# layer1.net
KiCad netlist of a schematic drawn in EAGLE
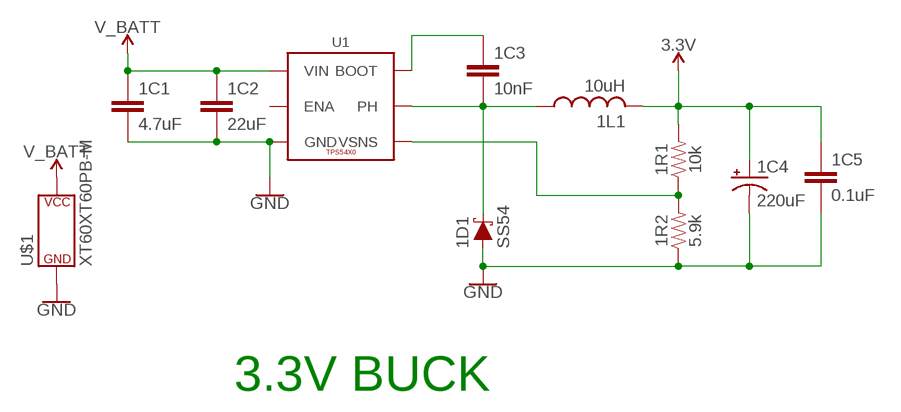
[diagram p0: schematic, sheet 1]
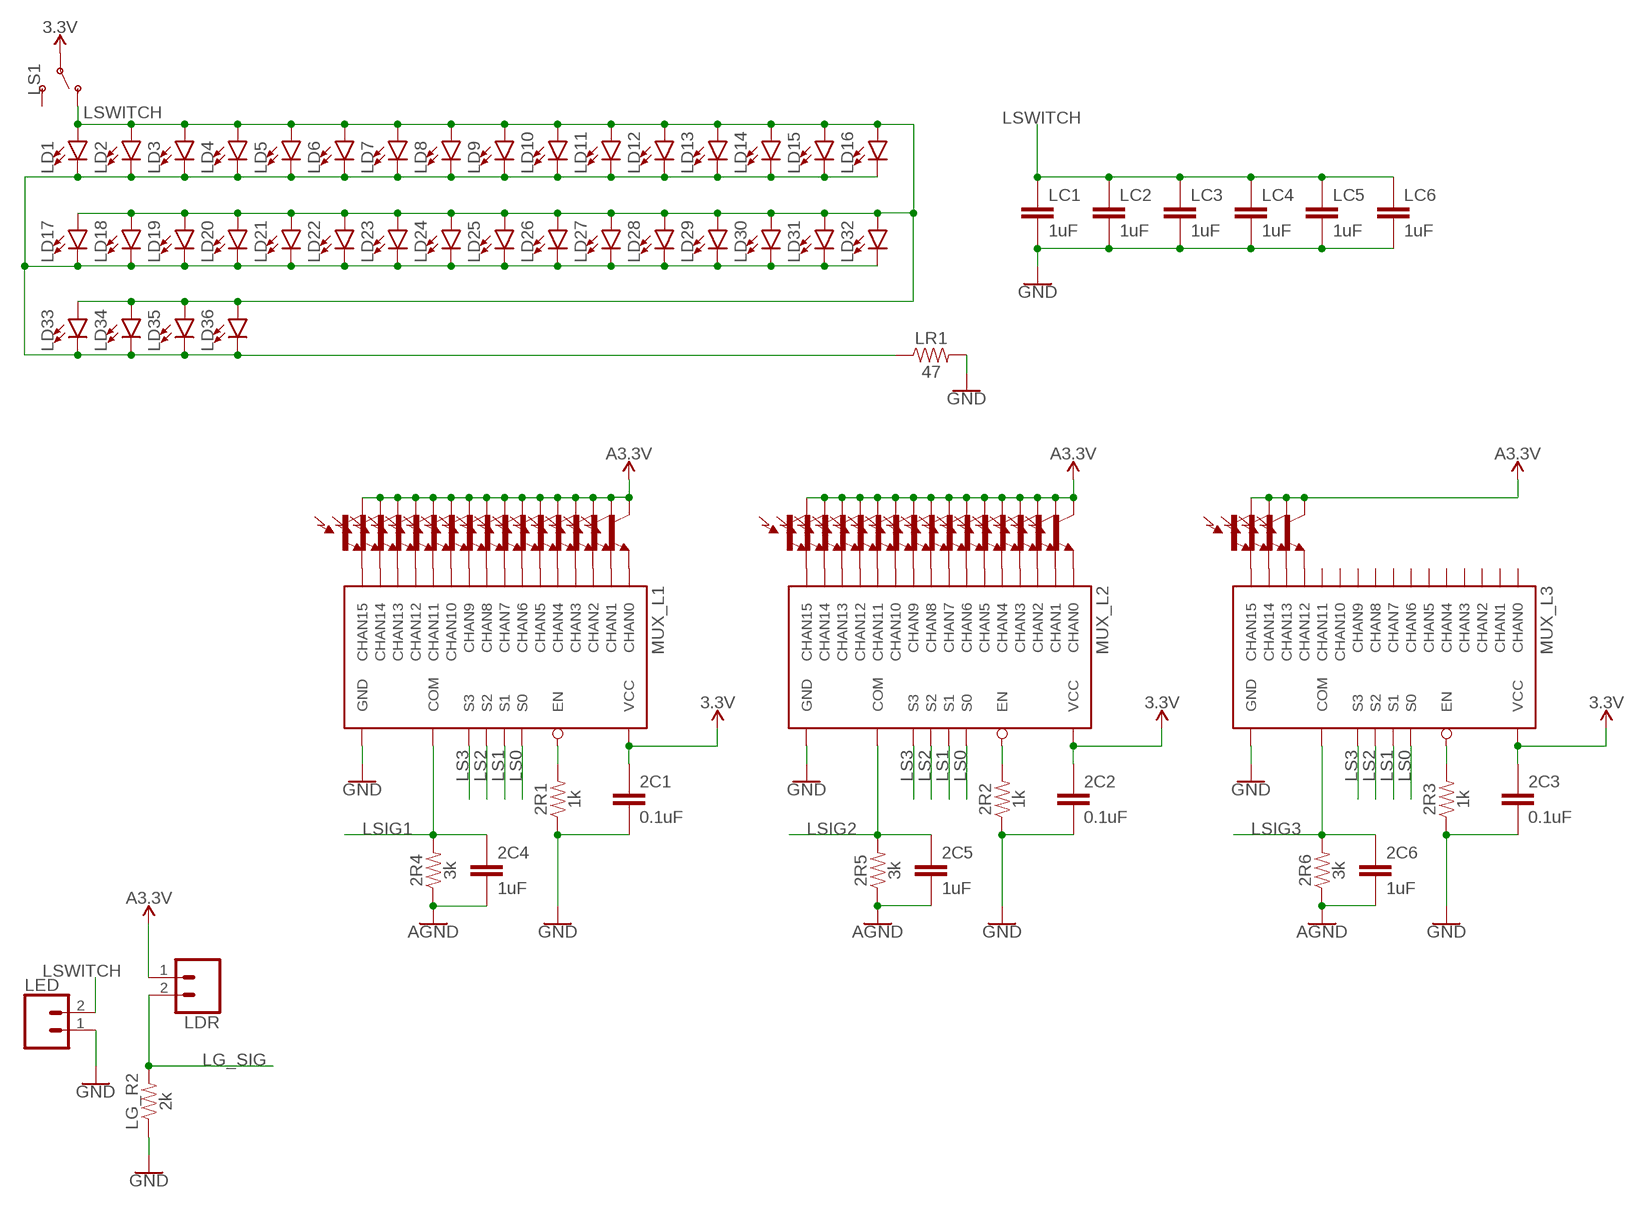
[diagram p1: schematic, sheet 2]
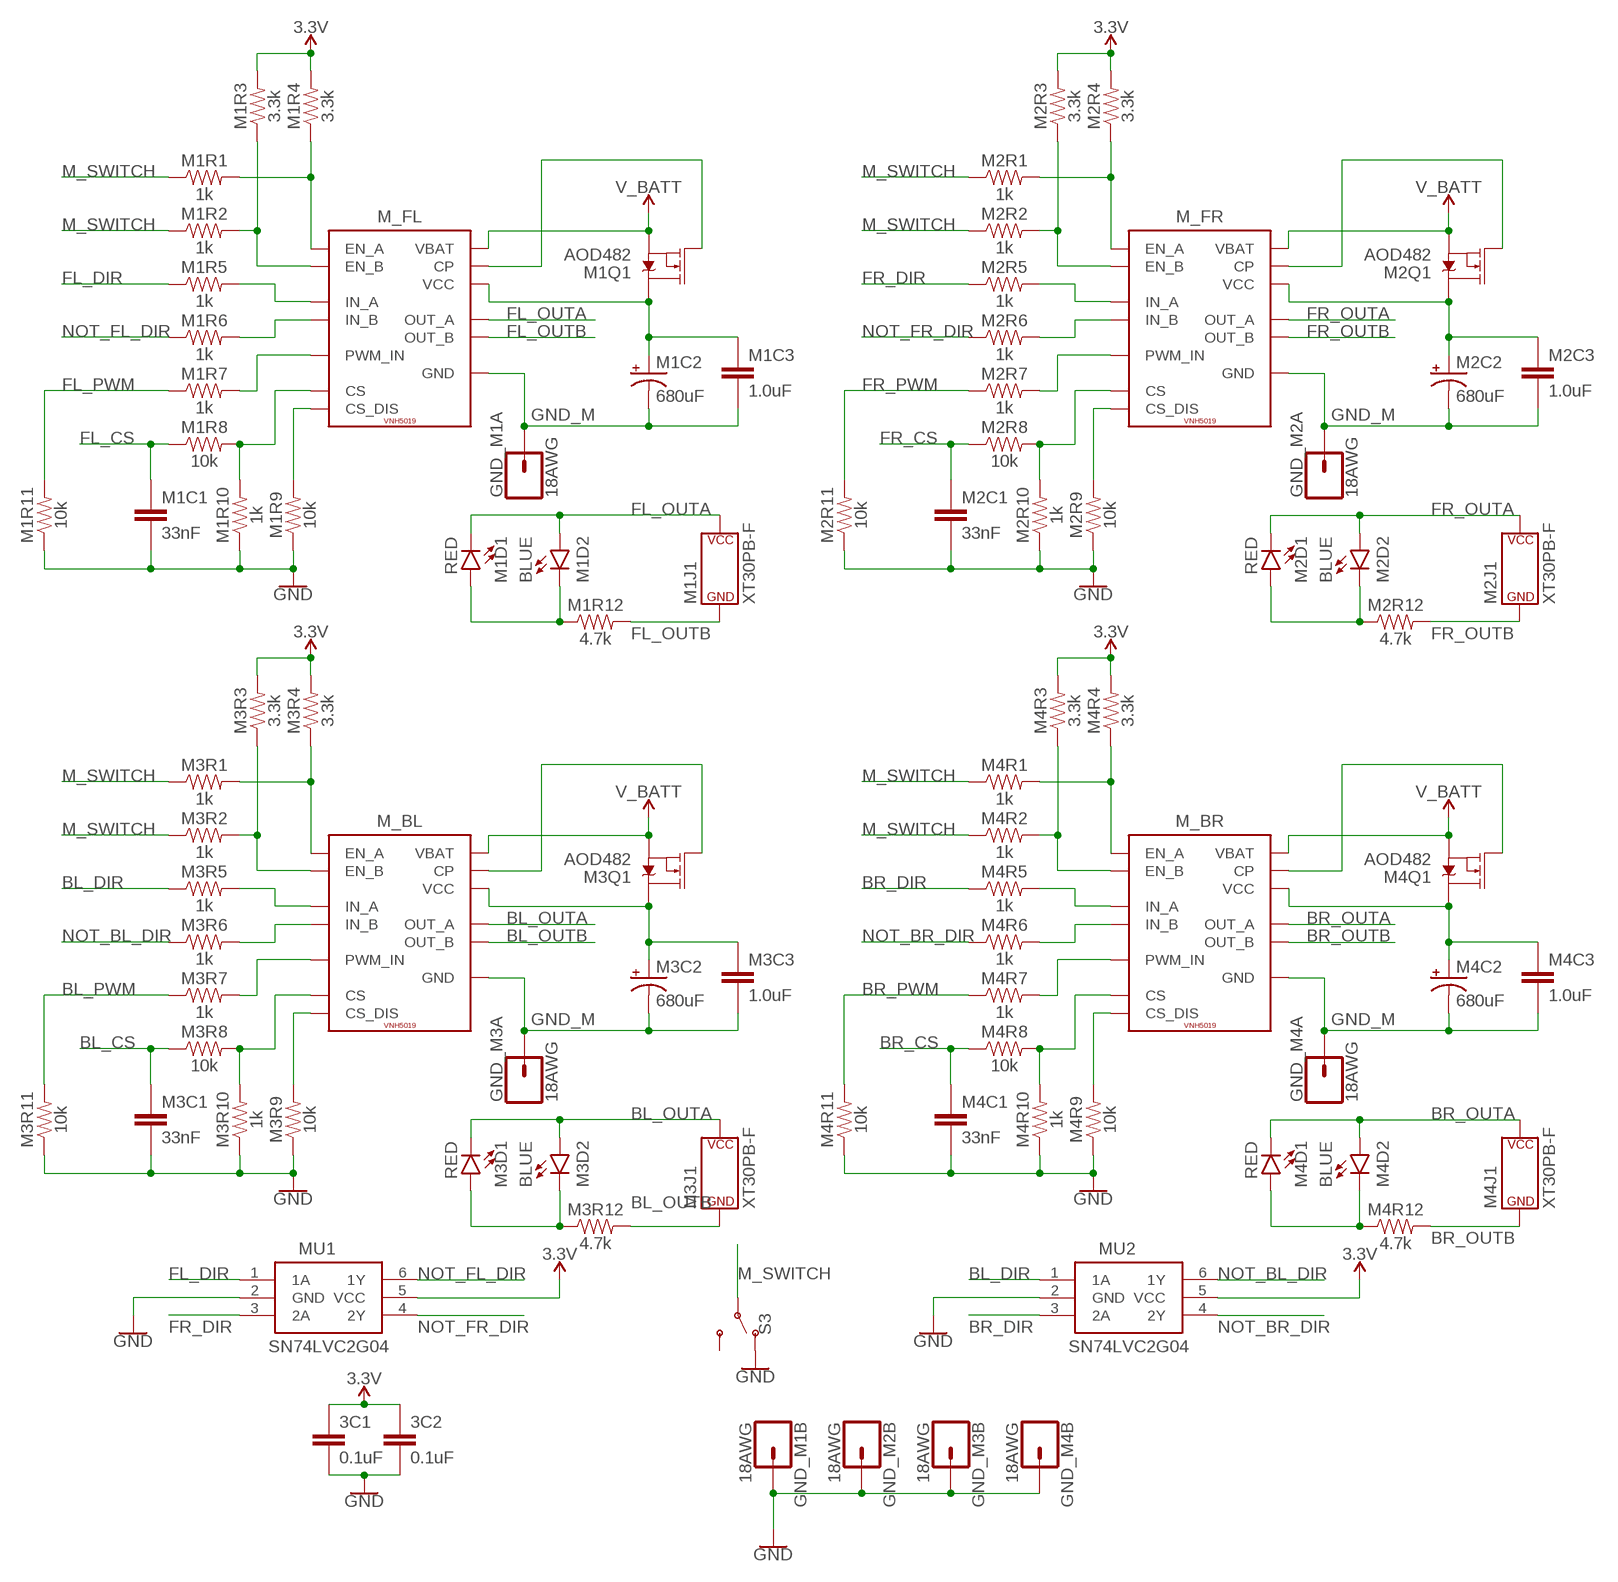
[diagram p2: schematic, sheet 3]
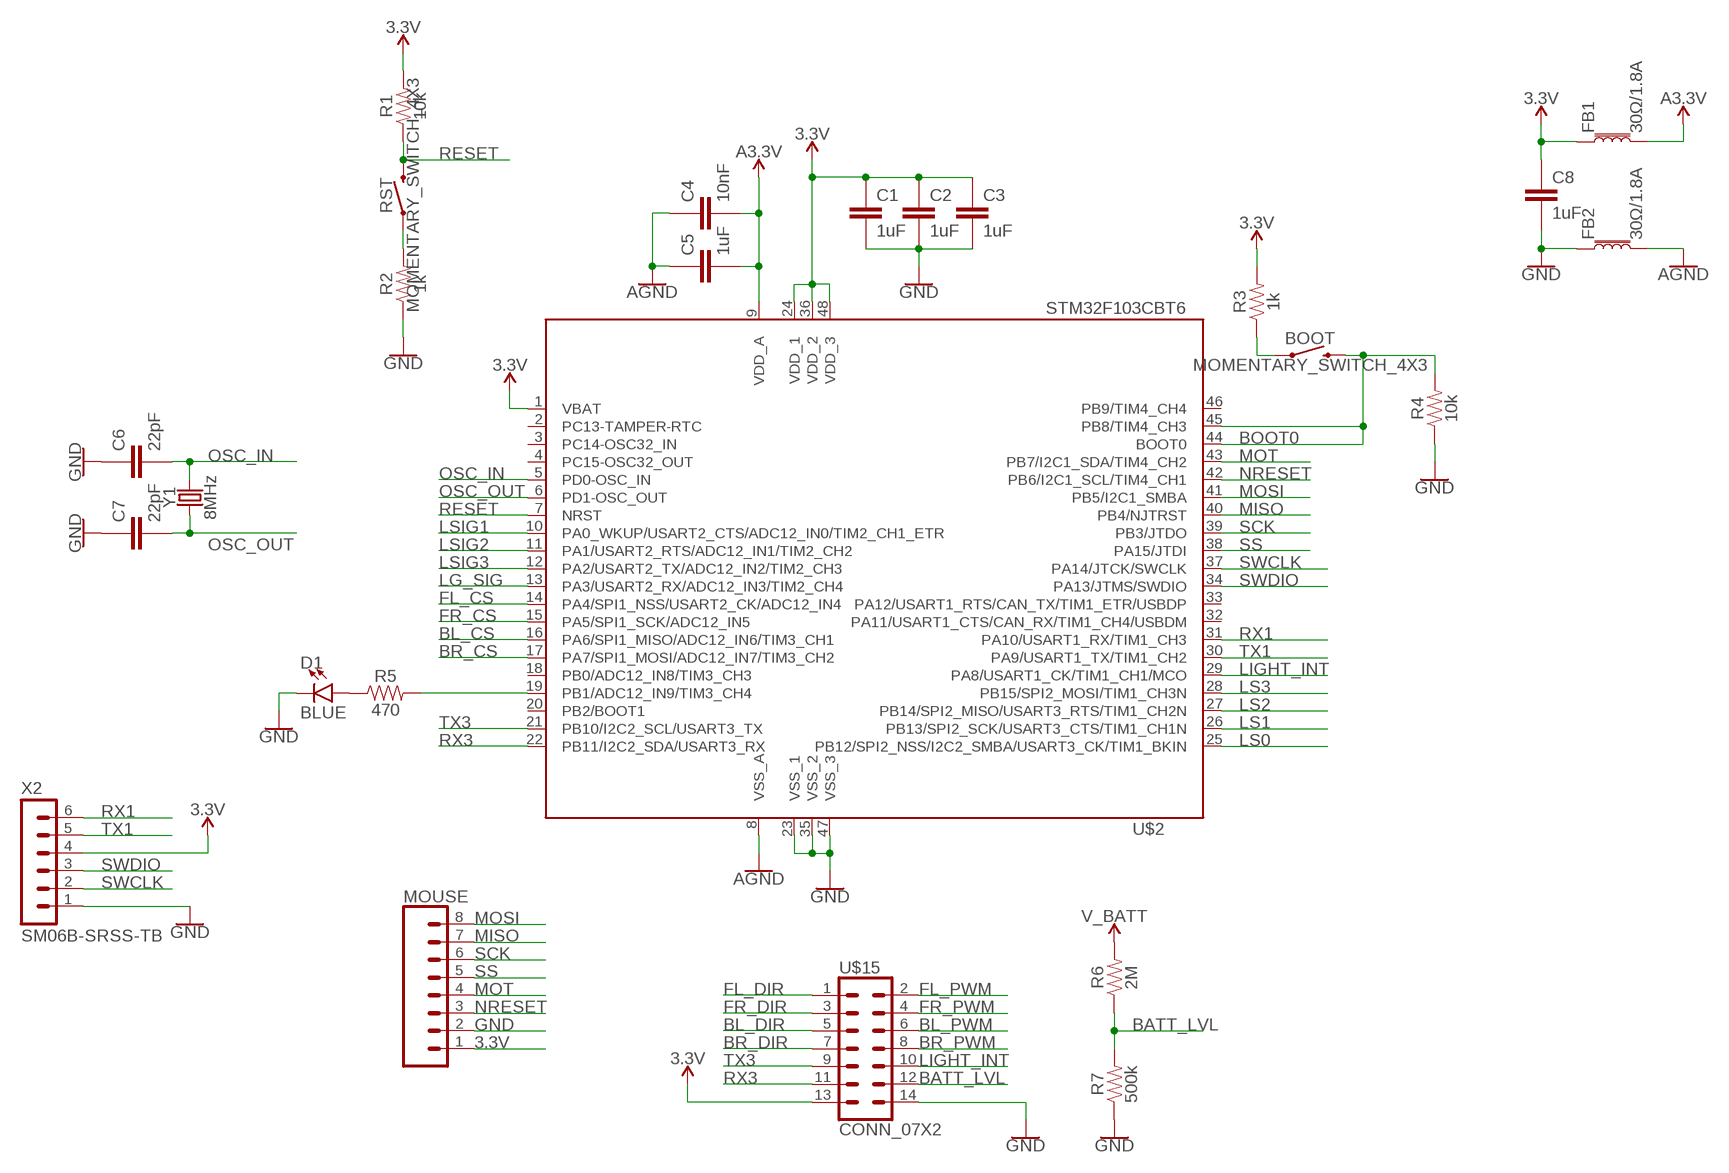
[diagram p3: schematic, sheet 4]

(export (version "E")
  (design (tool "Eeschema 10.0.6"))
  (components
    (comp (ref "3C1")
      (value "0.1uF")
      (footprint "eagle-import:C0603")
      (libsource (lib "eagle-import") (part "CAPACITOR0603"))
    )
    (comp (ref "3C2")
      (value "0.1uF")
      (footprint "eagle-import:C0603")
      (libsource (lib "eagle-import") (part "CAPACITOR0603"))
    )
    (comp (ref "GND_M1A")
      (value "18AWG")
      (footprint "eagle-import:18AWG")
      (libsource (lib "eagle-import") (part "18AWG"))
    )
    (comp (ref "GND_M1B")
      (value "18AWG")
      (footprint "eagle-import:18AWG")
      (libsource (lib "eagle-import") (part "18AWG"))
    )
    (comp (ref "GND_M2A")
      (value "18AWG")
      (footprint "eagle-import:18AWG")
      (libsource (lib "eagle-import") (part "18AWG"))
    )
    (comp (ref "GND_M2B")
      (value "18AWG")
      (footprint "eagle-import:18AWG")
      (libsource (lib "eagle-import") (part "18AWG"))
    )
    (comp (ref "GND_M3A")
      (value "18AWG")
      (footprint "eagle-import:18AWG")
      (libsource (lib "eagle-import") (part "18AWG"))
    )
    (comp (ref "GND_M3B")
      (value "18AWG")
      (footprint "eagle-import:18AWG")
      (libsource (lib "eagle-import") (part "18AWG"))
    )
    (comp (ref "GND_M4A")
      (value "18AWG")
      (footprint "eagle-import:18AWG")
      (libsource (lib "eagle-import") (part "18AWG"))
    )
    (comp (ref "GND_M4B")
      (value "18AWG")
      (footprint "eagle-import:18AWG")
      (libsource (lib "eagle-import") (part "18AWG"))
    )
    (comp (ref "M1C1")
      (value "33nF")
      (footprint "eagle-import:C0603")
      (libsource (lib "eagle-import") (part "CAPACITOR0603"))
    )
    (comp (ref "M1C2")
      (value "680uF")
      (footprint "eagle-import:3.5MM_CAP")
      (libsource (lib "eagle-import") (part "3.5MM_CAP"))
    )
    (comp (ref "M1C3")
      (value "1.0uF")
      (footprint "eagle-import:C0603")
      (libsource (lib "eagle-import") (part "CAPACITOR0603"))
    )
    (comp (ref "M1D1")
      (value "RED")
      (footprint "eagle-import:LED-0603")
      (libsource (lib "eagle-import") (part "LED-RED0603"))
    )
    (comp (ref "M1D2")
      (value "BLUE")
      (footprint "eagle-import:LED-0603")
      (libsource (lib "eagle-import") (part "LED-BLUE0603"))
    )
    (comp (ref "M1J1")
      (value "XT30PB-F")
      (footprint "eagle-import:XT30PB-F")
      (libsource (lib "eagle-import") (part "XT30PB-F"))
    )
    (comp (ref "M1Q1")
      (value "AOD482")
      (footprint "eagle-import:DPAK")
      (libsource (lib "eagle-import") (part "MOSFET-NCH-FDD8780"))
    )
    (comp (ref "M1R1")
      (value "1k")
      (footprint "eagle-import:R0603")
      (libsource (lib "eagle-import") (part "RESISTOR0603"))
    )
    (comp (ref "M1R2")
      (value "1k")
      (footprint "eagle-import:R0603")
      (libsource (lib "eagle-import") (part "RESISTOR0603"))
    )
    (comp (ref "M1R3")
      (value "3.3k")
      (footprint "eagle-import:R0603")
      (libsource (lib "eagle-import") (part "RESISTOR0603"))
    )
    (comp (ref "M1R4")
      (value "3.3k")
      (footprint "eagle-import:R0603")
      (libsource (lib "eagle-import") (part "RESISTOR0603"))
    )
    (comp (ref "M1R5")
      (value "1k")
      (footprint "eagle-import:R0603")
      (libsource (lib "eagle-import") (part "RESISTOR0603"))
    )
    (comp (ref "M1R6")
      (value "1k")
      (footprint "eagle-import:R0603")
      (libsource (lib "eagle-import") (part "RESISTOR0603"))
    )
    (comp (ref "M1R7")
      (value "1k")
      (footprint "eagle-import:R0603")
      (libsource (lib "eagle-import") (part "RESISTOR0603"))
    )
    (comp (ref "M1R8")
      (value "10k")
      (footprint "eagle-import:R0603")
      (libsource (lib "eagle-import") (part "RESISTOR0603"))
    )
    (comp (ref "M1R9")
      (value "10k")
      (footprint "eagle-import:R0603")
      (libsource (lib "eagle-import") (part "RESISTOR0603"))
    )
    (comp (ref "M1R10")
      (value "1k")
      (footprint "eagle-import:R0603")
      (libsource (lib "eagle-import") (part "RESISTOR0603"))
    )
    (comp (ref "M1R11")
      (value "10k")
      (footprint "eagle-import:R0603")
      (libsource (lib "eagle-import") (part "RESISTOR0603"))
    )
    (comp (ref "M1R12")
      (value "4.7k")
      (footprint "eagle-import:R0603")
      (libsource (lib "eagle-import") (part "RESISTOR0603"))
    )
    (comp (ref "M2C1")
      (value "33nF")
      (footprint "eagle-import:C0603")
      (libsource (lib "eagle-import") (part "CAPACITOR0603"))
    )
    (comp (ref "M2C2")
      (value "680uF")
      (footprint "eagle-import:3.5MM_CAP")
      (libsource (lib "eagle-import") (part "3.5MM_CAP"))
    )
    (comp (ref "M2C3")
      (value "1.0uF")
      (footprint "eagle-import:C0603")
      (libsource (lib "eagle-import") (part "CAPACITOR0603"))
    )
    (comp (ref "M2D1")
      (value "RED")
      (footprint "eagle-import:LED-0603")
      (libsource (lib "eagle-import") (part "LED-RED0603"))
    )
    (comp (ref "M2D2")
      (value "BLUE")
      (footprint "eagle-import:LED-0603")
      (libsource (lib "eagle-import") (part "LED-BLUE0603"))
    )
    (comp (ref "M2J1")
      (value "XT30PB-F")
      (footprint "eagle-import:XT30PB-F")
      (libsource (lib "eagle-import") (part "XT30PB-F"))
    )
    (comp (ref "M2Q1")
      (value "AOD482")
      (footprint "eagle-import:DPAK")
      (libsource (lib "eagle-import") (part "MOSFET-NCH-FDD8780"))
    )
    (comp (ref "M2R1")
      (value "1k")
      (footprint "eagle-import:R0603")
      (libsource (lib "eagle-import") (part "RESISTOR0603"))
    )
    (comp (ref "M2R2")
      (value "1k")
      (footprint "eagle-import:R0603")
      (libsource (lib "eagle-import") (part "RESISTOR0603"))
    )
    (comp (ref "M2R3")
      (value "3.3k")
      (footprint "eagle-import:R0603")
      (libsource (lib "eagle-import") (part "RESISTOR0603"))
    )
    (comp (ref "M2R4")
      (value "3.3k")
      (footprint "eagle-import:R0603")
      (libsource (lib "eagle-import") (part "RESISTOR0603"))
    )
    (comp (ref "M2R5")
      (value "1k")
      (footprint "eagle-import:R0603")
      (libsource (lib "eagle-import") (part "RESISTOR0603"))
    )
    (comp (ref "M2R6")
      (value "1k")
      (footprint "eagle-import:R0603")
      (libsource (lib "eagle-import") (part "RESISTOR0603"))
    )
    (comp (ref "M2R7")
      (value "1k")
      (footprint "eagle-import:R0603")
      (libsource (lib "eagle-import") (part "RESISTOR0603"))
    )
    (comp (ref "M2R8")
      (value "10k")
      (footprint "eagle-import:R0603")
      (libsource (lib "eagle-import") (part "RESISTOR0603"))
    )
    (comp (ref "M2R9")
      (value "10k")
      (footprint "eagle-import:R0603")
      (libsource (lib "eagle-import") (part "RESISTOR0603"))
    )
    (comp (ref "M2R10")
      (value "1k")
      (footprint "eagle-import:R0603")
      (libsource (lib "eagle-import") (part "RESISTOR0603"))
    )
    (comp (ref "M2R11")
      (value "10k")
      (footprint "eagle-import:R0603")
      (libsource (lib "eagle-import") (part "RESISTOR0603"))
    )
    (comp (ref "M2R12")
      (value "4.7k")
      (footprint "eagle-import:R0603")
      (libsource (lib "eagle-import") (part "RESISTOR0603"))
    )
    (comp (ref "M3C1")
      (value "33nF")
      (footprint "eagle-import:C0603")
      (libsource (lib "eagle-import") (part "CAPACITOR0603"))
    )
    (comp (ref "M3C2")
      (value "680uF")
      (footprint "eagle-import:3.5MM_CAP")
      (libsource (lib "eagle-import") (part "3.5MM_CAP"))
    )
    (comp (ref "M3C3")
      (value "1.0uF")
      (footprint "eagle-import:C0603")
      (libsource (lib "eagle-import") (part "CAPACITOR0603"))
    )
    (comp (ref "M3D1")
      (value "RED")
      (footprint "eagle-import:LED-0603")
      (libsource (lib "eagle-import") (part "LED-RED0603"))
    )
    (comp (ref "M3D2")
      (value "BLUE")
      (footprint "eagle-import:LED-0603")
      (libsource (lib "eagle-import") (part "LED-BLUE0603"))
    )
    (comp (ref "M3J1")
      (value "XT30PB-F")
      (footprint "eagle-import:XT30PB-F")
      (libsource (lib "eagle-import") (part "XT30PB-F"))
    )
    (comp (ref "M3Q1")
      (value "AOD482")
      (footprint "eagle-import:DPAK")
      (libsource (lib "eagle-import") (part "MOSFET-NCH-FDD8780"))
    )
    (comp (ref "M3R1")
      (value "1k")
      (footprint "eagle-import:R0603")
      (libsource (lib "eagle-import") (part "RESISTOR0603"))
    )
    (comp (ref "M3R2")
      (value "1k")
      (footprint "eagle-import:R0603")
      (libsource (lib "eagle-import") (part "RESISTOR0603"))
    )
    (comp (ref "M3R3")
      (value "3.3k")
      (footprint "eagle-import:R0603")
      (libsource (lib "eagle-import") (part "RESISTOR0603"))
    )
    (comp (ref "M3R4")
      (value "3.3k")
      (footprint "eagle-import:R0603")
      (libsource (lib "eagle-import") (part "RESISTOR0603"))
    )
    (comp (ref "M3R5")
      (value "1k")
      (footprint "eagle-import:R0603")
      (libsource (lib "eagle-import") (part "RESISTOR0603"))
    )
    (comp (ref "M3R6")
      (value "1k")
      (footprint "eagle-import:R0603")
      (libsource (lib "eagle-import") (part "RESISTOR0603"))
    )
    (comp (ref "M3R7")
      (value "1k")
      (footprint "eagle-import:R0603")
      (libsource (lib "eagle-import") (part "RESISTOR0603"))
    )
    (comp (ref "M3R8")
      (value "10k")
      (footprint "eagle-import:R0603")
      (libsource (lib "eagle-import") (part "RESISTOR0603"))
    )
    (comp (ref "M3R9")
      (value "10k")
      (footprint "eagle-import:R0603")
      (libsource (lib "eagle-import") (part "RESISTOR0603"))
    )
    (comp (ref "M3R10")
      (value "1k")
      (footprint "eagle-import:R0603")
      (libsource (lib "eagle-import") (part "RESISTOR0603"))
    )
    (comp (ref "M3R11")
      (value "10k")
      (footprint "eagle-import:R0603")
      (libsource (lib "eagle-import") (part "RESISTOR0603"))
    )
    (comp (ref "M3R12")
      (value "4.7k")
      (footprint "eagle-import:R0603")
      (libsource (lib "eagle-import") (part "RESISTOR0603"))
    )
    (comp (ref "M4C1")
      (value "33nF")
      (footprint "eagle-import:C0603")
      (libsource (lib "eagle-import") (part "CAPACITOR0603"))
    )
    (comp (ref "M4C2")
      (value "680uF")
      (footprint "eagle-import:3.5MM_CAP")
      (libsource (lib "eagle-import") (part "3.5MM_CAP"))
    )
    (comp (ref "M4C3")
      (value "1.0uF")
      (footprint "eagle-import:C0603")
      (libsource (lib "eagle-import") (part "CAPACITOR0603"))
    )
    (comp (ref "M4D1")
      (value "RED")
      (footprint "eagle-import:LED-0603")
      (libsource (lib "eagle-import") (part "LED-RED0603"))
    )
    (comp (ref "M4D2")
      (value "BLUE")
      (footprint "eagle-import:LED-0603")
      (libsource (lib "eagle-import") (part "LED-BLUE0603"))
    )
    (comp (ref "M4J1")
      (value "XT30PB-F")
      (footprint "eagle-import:XT30PB-F")
      (libsource (lib "eagle-import") (part "XT30PB-F"))
    )
    (comp (ref "M4Q1")
      (value "AOD482")
      (footprint "eagle-import:DPAK")
      (libsource (lib "eagle-import") (part "MOSFET-NCH-FDD8780"))
    )
    (comp (ref "M4R1")
      (value "1k")
      (footprint "eagle-import:R0603")
      (libsource (lib "eagle-import") (part "RESISTOR0603"))
    )
    (comp (ref "M4R2")
      (value "1k")
      (footprint "eagle-import:R0603")
      (libsource (lib "eagle-import") (part "RESISTOR0603"))
    )
    (comp (ref "M4R3")
      (value "3.3k")
      (footprint "eagle-import:R0603")
      (libsource (lib "eagle-import") (part "RESISTOR0603"))
    )
    (comp (ref "M4R4")
      (value "3.3k")
      (footprint "eagle-import:R0603")
      (libsource (lib "eagle-import") (part "RESISTOR0603"))
    )
    (comp (ref "M4R5")
      (value "1k")
      (footprint "eagle-import:R0603")
      (libsource (lib "eagle-import") (part "RESISTOR0603"))
    )
    (comp (ref "M4R6")
      (value "1k")
      (footprint "eagle-import:R0603")
      (libsource (lib "eagle-import") (part "RESISTOR0603"))
    )
    (comp (ref "M4R7")
      (value "1k")
      (footprint "eagle-import:R0603")
      (libsource (lib "eagle-import") (part "RESISTOR0603"))
    )
    (comp (ref "M4R8")
      (value "10k")
      (footprint "eagle-import:R0603")
      (libsource (lib "eagle-import") (part "RESISTOR0603"))
    )
    (comp (ref "M4R9")
      (value "10k")
      (footprint "eagle-import:R0603")
      (libsource (lib "eagle-import") (part "RESISTOR0603"))
    )
    (comp (ref "M4R10")
      (value "1k")
      (footprint "eagle-import:R0603")
      (libsource (lib "eagle-import") (part "RESISTOR0603"))
    )
    (comp (ref "M4R11")
      (value "10k")
      (footprint "eagle-import:R0603")
      (libsource (lib "eagle-import") (part "RESISTOR0603"))
    )
    (comp (ref "M4R12")
      (value "4.7k")
      (footprint "eagle-import:R0603")
      (libsource (lib "eagle-import") (part "RESISTOR0603"))
    )
    (comp (ref "MU1")
      (value "SN74LVC2G04DBVR")
      (footprint "eagle-import:SOT23-6")
      (libsource (lib "eagle-import") (part "SN74LVC2G04DBVR"))
    )
    (comp (ref "MU2")
      (value "SN74LVC2G04DBVR")
      (footprint "eagle-import:SOT23-6")
      (libsource (lib "eagle-import") (part "SN74LVC2G04DBVR"))
    )
    (comp (ref "M_BL")
      (value "VNH5019")
      (footprint "eagle-import:POWERSO-30")
      (libsource (lib "eagle-import") (part "VNH5019"))
    )
    (comp (ref "M_BR")
      (value "VNH5019")
      (footprint "eagle-import:POWERSO-30")
      (libsource (lib "eagle-import") (part "VNH5019"))
    )
    (comp (ref "M_FL")
      (value "VNH5019")
      (footprint "eagle-import:POWERSO-30")
      (libsource (lib "eagle-import") (part "VNH5019"))
    )
    (comp (ref "M_FR")
      (value "VNH5019")
      (footprint "eagle-import:POWERSO-30")
      (libsource (lib "eagle-import") (part "VNH5019"))
    )
    (comp (ref "S3")
      (value "SWITCH-SPDT-PTH-11.6X4.0MM-LOCK")
      (footprint "eagle-import:SWITCH_SPDT_PTH_11.6X4.0MM_LOCK")
      (libsource (lib "eagle-import") (part "SWITCH-SPDT-PTH-11.6X4.0MM-LOCK"))
    )
    (comp (ref "BOOT")
      (value "MOMENTARY_SWITCH_4X3")
      (footprint "eagle-import:MOMENTARY_SWITCH_4X3")
      (libsource (lib "eagle-import") (part "MOMENTARY_SWITCH_4X3"))
    )
    (comp (ref "C1")
      (value "1uF")
      (footprint "eagle-import:C0603")
      (libsource (lib "eagle-import") (part "CAPACITOR0603"))
    )
    (comp (ref "C2")
      (value "1uF")
      (footprint "eagle-import:C0603")
      (libsource (lib "eagle-import") (part "CAPACITOR0603"))
    )
    (comp (ref "C3")
      (value "1uF")
      (footprint "eagle-import:C0603")
      (libsource (lib "eagle-import") (part "CAPACITOR0603"))
    )
    (comp (ref "C4")
      (value "10nF")
      (footprint "eagle-import:C0603")
      (libsource (lib "eagle-import") (part "CAPACITOR0603"))
    )
    (comp (ref "C5")
      (value "1uF")
      (footprint "eagle-import:C0603")
      (libsource (lib "eagle-import") (part "CAPACITOR0603"))
    )
    (comp (ref "C6")
      (value "22pF")
      (footprint "eagle-import:C0603")
      (libsource (lib "eagle-import") (part "CAPACITOR0603"))
    )
    (comp (ref "C7")
      (value "22pF")
      (footprint "eagle-import:C0603")
      (libsource (lib "eagle-import") (part "CAPACITOR0603"))
    )
    (comp (ref "C8")
      (value "1uF")
      (footprint "eagle-import:C0603")
      (libsource (lib "eagle-import") (part "CAPACITOR0603"))
    )
    (comp (ref "D1")
      (value "BLUE")
      (footprint "eagle-import:LED-0603")
      (libsource (lib "eagle-import") (part "LED0603"))
    )
    (comp (ref "FB1")
      (value "30Ω/1.8A")
      (footprint "eagle-import:0603")
      (libsource (lib "eagle-import") (part "FERRITE_BEAD-0603"))
    )
    (comp (ref "FB2")
      (value "30Ω/1.8A")
      (footprint "eagle-import:0603")
      (libsource (lib "eagle-import") (part "FERRITE_BEAD-0603"))
    )
    (comp (ref "MOUSE")
      (value "CONN_08LOCK")
      (footprint "eagle-import:1X08_LOCK")
      (libsource (lib "eagle-import") (part "CONN_08LOCK"))
    )
    (comp (ref "R1")
      (value "10k")
      (footprint "eagle-import:R0603")
      (libsource (lib "eagle-import") (part "RESISTOR0603"))
    )
    (comp (ref "R2")
      (value "1k")
      (footprint "eagle-import:R0603")
      (libsource (lib "eagle-import") (part "RESISTOR0603"))
    )
    (comp (ref "R3")
      (value "1k")
      (footprint "eagle-import:R0603")
      (libsource (lib "eagle-import") (part "RESISTOR0603"))
    )
    (comp (ref "R4")
      (value "10k")
      (footprint "eagle-import:R0603")
      (libsource (lib "eagle-import") (part "RESISTOR0603"))
    )
    (comp (ref "R5")
      (value "470")
      (footprint "eagle-import:R0603")
      (libsource (lib "eagle-import") (part "RESISTOR0603"))
    )
    (comp (ref "R6")
      (value "2M")
      (footprint "eagle-import:R0603")
      (libsource (lib "eagle-import") (part "RESISTOR0603"))
    )
    (comp (ref "R7")
      (value "500k")
      (footprint "eagle-import:R0603")
      (libsource (lib "eagle-import") (part "RESISTOR0603"))
    )
    (comp (ref "RST")
      (value "MOMENTARY_SWITCH_4X3")
      (footprint "eagle-import:MOMENTARY_SWITCH_4X3")
      (libsource (lib "eagle-import") (part "MOMENTARY_SWITCH_4X3"))
    )
    (comp (ref "U$2")
      (value "STM32F103CBT6")
      (footprint "eagle-import:LQFP48")
      (libsource (lib "eagle-import") (part "STM32F103CBT6"))
    )
    (comp (ref "U$15")
      (value "CONN_07X2")
      (footprint "eagle-import:2X7")
      (libsource (lib "eagle-import") (part "CONN_07X2"))
    )
    (comp (ref "X2")
      (value "SM06B-SRSS-TB")
      (footprint "eagle-import:SM06B-SRSS-TB")
      (libsource (lib "eagle-import") (part "SM06B-SRSS-TB"))
    )
    (comp (ref "Y1")
      (value "8MHz")
      (footprint "eagle-import:CRYSTAL-SMD-5X3.2-2PAD")
      (libsource (lib "eagle-import") (part "CRYSTALSMD-5X3.2-2PAD"))
    )
    (comp (ref "2C1")
      (value "0.1uF")
      (footprint "eagle-import:C0603")
      (libsource (lib "eagle-import") (part "CAPACITOR0603"))
    )
    (comp (ref "2C2")
      (value "0.1uF")
      (footprint "eagle-import:C0603")
      (libsource (lib "eagle-import") (part "CAPACITOR0603"))
    )
    (comp (ref "2C3")
      (value "0.1uF")
      (footprint "eagle-import:C0603")
      (libsource (lib "eagle-import") (part "CAPACITOR0603"))
    )
    (comp (ref "2C4")
      (value "1uF")
      (footprint "eagle-import:C0603")
      (libsource (lib "eagle-import") (part "CAPACITOR0603"))
    )
    (comp (ref "2C5")
      (value "1uF")
      (footprint "eagle-import:C0603")
      (libsource (lib "eagle-import") (part "CAPACITOR0603"))
    )
    (comp (ref "2C6")
      (value "1uF")
      (footprint "eagle-import:C0603")
      (libsource (lib "eagle-import") (part "CAPACITOR0603"))
    )
    (comp (ref "2R1")
      (value "1k")
      (footprint "eagle-import:R0603")
      (libsource (lib "eagle-import") (part "RESISTOR0603"))
    )
    (comp (ref "2R2")
      (value "1k")
      (footprint "eagle-import:R0603")
      (libsource (lib "eagle-import") (part "RESISTOR0603"))
    )
    (comp (ref "2R3")
      (value "1k")
      (footprint "eagle-import:R0603")
      (libsource (lib "eagle-import") (part "RESISTOR0603"))
    )
    (comp (ref "2R4")
      (value "3k")
      (footprint "eagle-import:R0603")
      (libsource (lib "eagle-import") (part "RESISTOR0603"))
    )
    (comp (ref "2R5")
      (value "3k")
      (footprint "eagle-import:R0603")
      (libsource (lib "eagle-import") (part "RESISTOR0603"))
    )
    (comp (ref "2R6")
      (value "3k")
      (footprint "eagle-import:R0603")
      (libsource (lib "eagle-import") (part "RESISTOR0603"))
    )
    (comp (ref "LC1")
      (value "1uF")
      (footprint "eagle-import:C0603")
      (libsource (lib "eagle-import") (part "CAPACITOR0603"))
    )
    (comp (ref "LC2")
      (value "1uF")
      (footprint "eagle-import:C0603")
      (libsource (lib "eagle-import") (part "CAPACITOR0603"))
    )
    (comp (ref "LC3")
      (value "1uF")
      (footprint "eagle-import:C0603")
      (libsource (lib "eagle-import") (part "CAPACITOR0603"))
    )
    (comp (ref "LC4")
      (value "1uF")
      (footprint "eagle-import:C0603")
      (libsource (lib "eagle-import") (part "CAPACITOR0603"))
    )
    (comp (ref "LC5")
      (value "1uF")
      (footprint "eagle-import:C0603")
      (libsource (lib "eagle-import") (part "CAPACITOR0603"))
    )
    (comp (ref "LC6")
      (value "1uF")
      (footprint "eagle-import:C0603")
      (libsource (lib "eagle-import") (part "CAPACITOR0603"))
    )
    (comp (ref "LD1")
      (value "3528LED")
      (footprint "eagle-import:3528")
      (libsource (lib "eagle-import") (part "3528LED"))
    )
    (comp (ref "LD2")
      (value "3528LED")
      (footprint "eagle-import:3528")
      (libsource (lib "eagle-import") (part "3528LED"))
    )
    (comp (ref "LD3")
      (value "3528LED")
      (footprint "eagle-import:3528")
      (libsource (lib "eagle-import") (part "3528LED"))
    )
    (comp (ref "LD4")
      (value "3528LED")
      (footprint "eagle-import:3528")
      (libsource (lib "eagle-import") (part "3528LED"))
    )
    (comp (ref "LD5")
      (value "3528LED")
      (footprint "eagle-import:3528")
      (libsource (lib "eagle-import") (part "3528LED"))
    )
    (comp (ref "LD6")
      (value "3528LED")
      (footprint "eagle-import:3528")
      (libsource (lib "eagle-import") (part "3528LED"))
    )
    (comp (ref "LD7")
      (value "3528LED")
      (footprint "eagle-import:3528")
      (libsource (lib "eagle-import") (part "3528LED"))
    )
    (comp (ref "LD8")
      (value "3528LED")
      (footprint "eagle-import:3528")
      (libsource (lib "eagle-import") (part "3528LED"))
    )
    (comp (ref "LD9")
      (value "3528LED")
      (footprint "eagle-import:3528")
      (libsource (lib "eagle-import") (part "3528LED"))
    )
    (comp (ref "LD10")
      (value "3528LED")
      (footprint "eagle-import:3528")
      (libsource (lib "eagle-import") (part "3528LED"))
    )
    (comp (ref "LD11")
      (value "3528LED")
      (footprint "eagle-import:3528")
      (libsource (lib "eagle-import") (part "3528LED"))
    )
    (comp (ref "LD12")
      (value "3528LED")
      (footprint "eagle-import:3528")
      (libsource (lib "eagle-import") (part "3528LED"))
    )
    (comp (ref "LD13")
      (value "3528LED")
      (footprint "eagle-import:3528")
      (libsource (lib "eagle-import") (part "3528LED"))
    )
    (comp (ref "LD14")
      (value "3528LED")
      (footprint "eagle-import:3528")
      (libsource (lib "eagle-import") (part "3528LED"))
    )
    (comp (ref "LD15")
      (value "3528LED")
      (footprint "eagle-import:3528")
      (libsource (lib "eagle-import") (part "3528LED"))
    )
    (comp (ref "LD16")
      (value "3528LED")
      (footprint "eagle-import:3528")
      (libsource (lib "eagle-import") (part "3528LED"))
    )
    (comp (ref "LD17")
      (value "3528LED")
      (footprint "eagle-import:3528")
      (libsource (lib "eagle-import") (part "3528LED"))
    )
    (comp (ref "LD18")
      (value "3528LED")
      (footprint "eagle-import:3528")
      (libsource (lib "eagle-import") (part "3528LED"))
    )
    (comp (ref "LD19")
      (value "3528LED")
      (footprint "eagle-import:3528")
      (libsource (lib "eagle-import") (part "3528LED"))
    )
    (comp (ref "LD20")
      (value "3528LED")
      (footprint "eagle-import:3528")
      (libsource (lib "eagle-import") (part "3528LED"))
    )
    (comp (ref "LD21")
      (value "3528LED")
      (footprint "eagle-import:3528")
      (libsource (lib "eagle-import") (part "3528LED"))
    )
    (comp (ref "LD22")
      (value "3528LED")
      (footprint "eagle-import:3528")
      (libsource (lib "eagle-import") (part "3528LED"))
    )
    (comp (ref "LD23")
      (value "3528LED")
      (footprint "eagle-import:3528")
      (libsource (lib "eagle-import") (part "3528LED"))
    )
    (comp (ref "LD24")
      (value "3528LED")
      (footprint "eagle-import:3528")
      (libsource (lib "eagle-import") (part "3528LED"))
    )
    (comp (ref "LD25")
      (value "3528LED")
      (footprint "eagle-import:3528")
      (libsource (lib "eagle-import") (part "3528LED"))
    )
    (comp (ref "LD26")
      (value "3528LED")
      (footprint "eagle-import:3528")
      (libsource (lib "eagle-import") (part "3528LED"))
    )
    (comp (ref "LD27")
      (value "3528LED")
      (footprint "eagle-import:3528")
      (libsource (lib "eagle-import") (part "3528LED"))
    )
    (comp (ref "LD28")
      (value "3528LED")
      (footprint "eagle-import:3528")
      (libsource (lib "eagle-import") (part "3528LED"))
    )
    (comp (ref "LD29")
      (value "3528LED")
      (footprint "eagle-import:3528")
      (libsource (lib "eagle-import") (part "3528LED"))
    )
    (comp (ref "LD30")
      (value "3528LED")
      (footprint "eagle-import:3528")
      (libsource (lib "eagle-import") (part "3528LED"))
    )
    (comp (ref "LD31")
      (value "3528LED")
      (footprint "eagle-import:3528")
      (libsource (lib "eagle-import") (part "3528LED"))
    )
    (comp (ref "LD32")
      (value "3528LED")
      (footprint "eagle-import:3528")
      (libsource (lib "eagle-import") (part "3528LED"))
    )
    (comp (ref "LD33")
      (value "3528LED")
      (footprint "eagle-import:3528")
      (libsource (lib "eagle-import") (part "3528LED"))
    )
    (comp (ref "LD34")
      (value "3528LED")
      (footprint "eagle-import:3528")
      (libsource (lib "eagle-import") (part "3528LED"))
    )
    (comp (ref "LD35")
      (value "3528LED")
      (footprint "eagle-import:3528")
      (libsource (lib "eagle-import") (part "3528LED"))
    )
    (comp (ref "LD36")
      (value "3528LED")
      (footprint "eagle-import:3528")
      (libsource (lib "eagle-import") (part "3528LED"))
    )
    (comp (ref "LDR")
      (value "CONN_021X02_NO_SILK")
      (footprint "eagle-import:1X02_NO_SILK")
      (libsource (lib "eagle-import") (part "CONN_021X02_NO_SILK"))
    )
    (comp (ref "LED")
      (value "CONN_02POLAR")
      (footprint "eagle-import:MOLEX-1X2")
      (libsource (lib "eagle-import") (part "CONN_02POLAR"))
    )
    (comp (ref "LG_R2")
      (value "2k")
      (footprint "eagle-import:R0603")
      (libsource (lib "eagle-import") (part "RESISTOR0603"))
    )
    (comp (ref "LR1")
      (value "47")
      (footprint "eagle-import:R0603")
      (libsource (lib "eagle-import") (part "RESISTOR0603"))
    )
    (comp (ref "LS1")
      (value "SWITCH-SPDT-PTH-11.6X4.0MM-LOCK")
      (footprint "eagle-import:SWITCH_SPDT_PTH_11.6X4.0MM_LOCK")
      (libsource (lib "eagle-import") (part "SWITCH-SPDT-PTH-11.6X4.0MM-LOCK"))
    )
    (comp (ref "MUX_L1")
      (value "74HC4067SSOP-24")
      (footprint "eagle-import:SSOP24")
      (libsource (lib "eagle-import") (part "74HC4067SSOP-24"))
    )
    (comp (ref "MUX_L2")
      (value "74HC4067SSOP-24")
      (footprint "eagle-import:SSOP24")
      (libsource (lib "eagle-import") (part "74HC4067SSOP-24"))
    )
    (comp (ref "MUX_L3")
      (value "74HC4067SSOP-24")
      (footprint "eagle-import:SSOP24")
      (libsource (lib "eagle-import") (part "74HC4067SSOP-24"))
    )
    (comp (ref "Q1")
      (value "LIGHT_SENSORALS")
      (footprint "eagle-import:ALS-PT19")
      (libsource (lib "eagle-import") (part "LIGHT_SENSORALS"))
    )
    (comp (ref "Q2")
      (value "LIGHT_SENSORALS")
      (footprint "eagle-import:ALS-PT19")
      (libsource (lib "eagle-import") (part "LIGHT_SENSORALS"))
    )
    (comp (ref "Q3")
      (value "LIGHT_SENSORALS")
      (footprint "eagle-import:ALS-PT19")
      (libsource (lib "eagle-import") (part "LIGHT_SENSORALS"))
    )
    (comp (ref "Q4")
      (value "LIGHT_SENSORALS")
      (footprint "eagle-import:ALS-PT19")
      (libsource (lib "eagle-import") (part "LIGHT_SENSORALS"))
    )
    (comp (ref "Q5")
      (value "LIGHT_SENSORALS")
      (footprint "eagle-import:ALS-PT19")
      (libsource (lib "eagle-import") (part "LIGHT_SENSORALS"))
    )
    (comp (ref "Q6")
      (value "LIGHT_SENSORALS")
      (footprint "eagle-import:ALS-PT19")
      (libsource (lib "eagle-import") (part "LIGHT_SENSORALS"))
    )
    (comp (ref "Q7")
      (value "LIGHT_SENSORALS")
      (footprint "eagle-import:ALS-PT19")
      (libsource (lib "eagle-import") (part "LIGHT_SENSORALS"))
    )
    (comp (ref "Q8")
      (value "LIGHT_SENSORALS")
      (footprint "eagle-import:ALS-PT19")
      (libsource (lib "eagle-import") (part "LIGHT_SENSORALS"))
    )
    (comp (ref "Q9")
      (value "LIGHT_SENSORALS")
      (footprint "eagle-import:ALS-PT19")
      (libsource (lib "eagle-import") (part "LIGHT_SENSORALS"))
    )
    (comp (ref "Q10")
      (value "LIGHT_SENSORALS")
      (footprint "eagle-import:ALS-PT19")
      (libsource (lib "eagle-import") (part "LIGHT_SENSORALS"))
    )
    (comp (ref "Q11")
      (value "LIGHT_SENSORALS")
      (footprint "eagle-import:ALS-PT19")
      (libsource (lib "eagle-import") (part "LIGHT_SENSORALS"))
    )
    (comp (ref "Q12")
      (value "LIGHT_SENSORALS")
      (footprint "eagle-import:ALS-PT19")
      (libsource (lib "eagle-import") (part "LIGHT_SENSORALS"))
    )
    (comp (ref "Q13")
      (value "LIGHT_SENSORALS")
      (footprint "eagle-import:ALS-PT19")
      (libsource (lib "eagle-import") (part "LIGHT_SENSORALS"))
    )
    (comp (ref "Q14")
      (value "LIGHT_SENSORALS")
      (footprint "eagle-import:ALS-PT19")
      (libsource (lib "eagle-import") (part "LIGHT_SENSORALS"))
    )
    (comp (ref "Q15")
      (value "LIGHT_SENSORALS")
      (footprint "eagle-import:ALS-PT19")
      (libsource (lib "eagle-import") (part "LIGHT_SENSORALS"))
    )
    (comp (ref "Q16")
      (value "LIGHT_SENSORALS")
      (footprint "eagle-import:ALS-PT19")
      (libsource (lib "eagle-import") (part "LIGHT_SENSORALS"))
    )
    (comp (ref "Q17")
      (value "LIGHT_SENSORALS")
      (footprint "eagle-import:ALS-PT19")
      (libsource (lib "eagle-import") (part "LIGHT_SENSORALS"))
    )
    (comp (ref "Q18")
      (value "LIGHT_SENSORALS")
      (footprint "eagle-import:ALS-PT19")
      (libsource (lib "eagle-import") (part "LIGHT_SENSORALS"))
    )
    (comp (ref "Q19")
      (value "LIGHT_SENSORALS")
      (footprint "eagle-import:ALS-PT19")
      (libsource (lib "eagle-import") (part "LIGHT_SENSORALS"))
    )
    (comp (ref "Q20")
      (value "LIGHT_SENSORALS")
      (footprint "eagle-import:ALS-PT19")
      (libsource (lib "eagle-import") (part "LIGHT_SENSORALS"))
    )
    (comp (ref "Q21")
      (value "LIGHT_SENSORALS")
      (footprint "eagle-import:ALS-PT19")
      (libsource (lib "eagle-import") (part "LIGHT_SENSORALS"))
    )
    (comp (ref "Q22")
      (value "LIGHT_SENSORALS")
      (footprint "eagle-import:ALS-PT19")
      (libsource (lib "eagle-import") (part "LIGHT_SENSORALS"))
    )
    (comp (ref "Q23")
      (value "LIGHT_SENSORALS")
      (footprint "eagle-import:ALS-PT19")
      (libsource (lib "eagle-import") (part "LIGHT_SENSORALS"))
    )
    (comp (ref "Q24")
      (value "LIGHT_SENSORALS")
      (footprint "eagle-import:ALS-PT19")
      (libsource (lib "eagle-import") (part "LIGHT_SENSORALS"))
    )
    (comp (ref "Q25")
      (value "LIGHT_SENSORALS")
      (footprint "eagle-import:ALS-PT19")
      (libsource (lib "eagle-import") (part "LIGHT_SENSORALS"))
    )
    (comp (ref "Q26")
      (value "LIGHT_SENSORALS")
      (footprint "eagle-import:ALS-PT19")
      (libsource (lib "eagle-import") (part "LIGHT_SENSORALS"))
    )
    (comp (ref "Q27")
      (value "LIGHT_SENSORALS")
      (footprint "eagle-import:ALS-PT19")
      (libsource (lib "eagle-import") (part "LIGHT_SENSORALS"))
    )
    (comp (ref "Q28")
      (value "LIGHT_SENSORALS")
      (footprint "eagle-import:ALS-PT19")
      (libsource (lib "eagle-import") (part "LIGHT_SENSORALS"))
    )
    (comp (ref "Q29")
      (value "LIGHT_SENSORALS")
      (footprint "eagle-import:ALS-PT19")
      (libsource (lib "eagle-import") (part "LIGHT_SENSORALS"))
    )
    (comp (ref "Q30")
      (value "LIGHT_SENSORALS")
      (footprint "eagle-import:ALS-PT19")
      (libsource (lib "eagle-import") (part "LIGHT_SENSORALS"))
    )
    (comp (ref "Q31")
      (value "LIGHT_SENSORALS")
      (footprint "eagle-import:ALS-PT19")
      (libsource (lib "eagle-import") (part "LIGHT_SENSORALS"))
    )
    (comp (ref "Q32")
      (value "LIGHT_SENSORALS")
      (footprint "eagle-import:ALS-PT19")
      (libsource (lib "eagle-import") (part "LIGHT_SENSORALS"))
    )
    (comp (ref "Q33")
      (value "LIGHT_SENSORALS")
      (footprint "eagle-import:ALS-PT19")
      (libsource (lib "eagle-import") (part "LIGHT_SENSORALS"))
    )
    (comp (ref "Q34")
      (value "LIGHT_SENSORALS")
      (footprint "eagle-import:ALS-PT19")
      (libsource (lib "eagle-import") (part "LIGHT_SENSORALS"))
    )
    (comp (ref "Q35")
      (value "LIGHT_SENSORALS")
      (footprint "eagle-import:ALS-PT19")
      (libsource (lib "eagle-import") (part "LIGHT_SENSORALS"))
    )
    (comp (ref "Q36")
      (value "LIGHT_SENSORALS")
      (footprint "eagle-import:ALS-PT19")
      (libsource (lib "eagle-import") (part "LIGHT_SENSORALS"))
    )
    (comp (ref "1C1")
      (value "4.7uF")
      (footprint "eagle-import:C0603")
      (libsource (lib "eagle-import") (part "CAPACITOR0603"))
    )
    (comp (ref "1C2")
      (value "22uF")
      (footprint "eagle-import:C1210")
      (libsource (lib "eagle-import") (part "CAPACITOR1210"))
    )
    (comp (ref "1C3")
      (value "10nF")
      (footprint "eagle-import:C0603")
      (libsource (lib "eagle-import") (part "CAPACITOR0603"))
    )
    (comp (ref "1C4")
      (value "220uF")
      (footprint "eagle-import:EIA7343")
      (libsource (lib "eagle-import") (part "100UF-POLAR-EIA7343-10V-10%(TANT)"))
    )
    (comp (ref "1C5")
      (value "0.1uF")
      (footprint "eagle-import:C0603")
      (libsource (lib "eagle-import") (part "CAPACITOR0603"))
    )
    (comp (ref "1D1")
      (value "SS54")
      (footprint "eagle-import:SMA-DIODE")
      (libsource (lib "eagle-import") (part "DIODE-SCHOTTKY"))
    )
    (comp (ref "1L1")
      (value "10uH")
      (footprint "eagle-import:SWPA8040")
      (libsource (lib "eagle-import") (part "INDUCTORSWPA8040"))
    )
    (comp (ref "1R1")
      (value "10k")
      (footprint "eagle-import:R0603")
      (libsource (lib "eagle-import") (part "RESISTOR0603"))
    )
    (comp (ref "1R2")
      (value "5.9k")
      (footprint "eagle-import:R0603")
      (libsource (lib "eagle-import") (part "RESISTOR0603"))
    )
    (comp (ref "U$1")
      (value "XT60XT60PB-M")
      (footprint "eagle-import:XT60PB-M")
      (libsource (lib "eagle-import") (part "XT60XT60PB-M"))
    )
    (comp (ref "U1")
      (value "TPS54X0")
      (footprint "eagle-import:POWERPAD-SOIC-8")
      (libsource (lib "eagle-import") (part "TPS54X0"))
    )
  )
  (nets
    (net (code "1") (name "3.3V") (class "Default")
      (node (ref "1C4") (pin "A") (pinfunction "+_A") (pintype "passive"))
      (node (ref "1C5") (pin "1") (pinfunction "1_1") (pintype "passive"))
      (node (ref "1L1") (pin "P2") (pinfunction "2_P2") (pintype "passive"))
      (node (ref "1R1") (pin "2") (pinfunction "2_2") (pintype "passive"))
      (node (ref "2C1") (pin "1") (pinfunction "1_1") (pintype "passive"))
      (node (ref "2C2") (pin "1") (pinfunction "1_1") (pintype "passive"))
      (node (ref "2C3") (pin "1") (pinfunction "1_1") (pintype "passive"))
      (node (ref "3C1") (pin "1") (pinfunction "1_1") (pintype "passive"))
      (node (ref "3C2") (pin "1") (pinfunction "1_1") (pintype "passive"))
      (node (ref "C1") (pin "1") (pinfunction "1_1") (pintype "passive"))
      (node (ref "C2") (pin "1") (pinfunction "1_1") (pintype "passive"))
      (node (ref "C3") (pin "1") (pinfunction "1_1") (pintype "passive"))
      (node (ref "C8") (pin "1") (pinfunction "1_1") (pintype "passive"))
      (node (ref "FB1") (pin "1") (pinfunction "1_1") (pintype "passive"))
      (node (ref "LS1") (pin "2") (pinfunction "P_2") (pintype "passive"))
      (node (ref "M1R3") (pin "2") (pinfunction "2_2") (pintype "passive"))
      (node (ref "M1R4") (pin "2") (pinfunction "2_2") (pintype "passive"))
      (node (ref "M2R3") (pin "2") (pinfunction "2_2") (pintype "passive"))
      (node (ref "M2R4") (pin "2") (pinfunction "2_2") (pintype "passive"))
      (node (ref "M3R3") (pin "2") (pinfunction "2_2") (pintype "passive"))
      (node (ref "M3R4") (pin "2") (pinfunction "2_2") (pintype "passive"))
      (node (ref "M4R3") (pin "2") (pinfunction "2_2") (pintype "passive"))
      (node (ref "M4R4") (pin "2") (pinfunction "2_2") (pintype "passive"))
      (node (ref "MOUSE") (pin "1") (pinfunction "1_1") (pintype "passive"))
      (node (ref "MU1") (pin "5") (pinfunction "VCC_5") (pintype "bidirectional"))
      (node (ref "MU2") (pin "5") (pinfunction "VCC_5") (pintype "bidirectional"))
      (node (ref "MUX_L1") (pin "24") (pinfunction "VCC_24") (pintype "bidirectional"))
      (node (ref "MUX_L2") (pin "24") (pinfunction "VCC_24") (pintype "bidirectional"))
      (node (ref "MUX_L3") (pin "24") (pinfunction "VCC_24") (pintype "bidirectional"))
      (node (ref "R1") (pin "2") (pinfunction "2_2") (pintype "passive"))
      (node (ref "R3") (pin "2") (pinfunction "2_2") (pintype "passive"))
      (node (ref "U$15") (pin "13") (pinfunction "13_13") (pintype "passive"))
      (node (ref "U$2") (pin "1") (pinfunction "VBAT_1") (pintype "power_in"))
      (node (ref "U$2") (pin "24") (pinfunction "VDD_1_24") (pintype "power_in"))
      (node (ref "U$2") (pin "36") (pinfunction "VDD_2_36") (pintype "power_in"))
      (node (ref "U$2") (pin "48") (pinfunction "VDD_3_48") (pintype "power_in"))
      (node (ref "X2") (pin "4") (pinfunction "4_4") (pintype "passive"))
    )
    (net (code "2") (name "AGND") (class "Default")
      (node (ref "2C4") (pin "2") (pinfunction "2_2") (pintype "passive"))
      (node (ref "2C5") (pin "2") (pinfunction "2_2") (pintype "passive"))
      (node (ref "2C6") (pin "2") (pinfunction "2_2") (pintype "passive"))
      (node (ref "2R4") (pin "1") (pinfunction "1_1") (pintype "passive"))
      (node (ref "2R5") (pin "1") (pinfunction "1_1") (pintype "passive"))
      (node (ref "2R6") (pin "1") (pinfunction "1_1") (pintype "passive"))
      (node (ref "C4") (pin "1") (pinfunction "1_1") (pintype "passive"))
      (node (ref "C5") (pin "1") (pinfunction "1_1") (pintype "passive"))
      (node (ref "FB2") (pin "2") (pinfunction "2_2") (pintype "passive"))
      (node (ref "U$2") (pin "8") (pinfunction "VSS_A_8") (pintype "power_in"))
    )
    (net (code "3") (name "BATT_LVL") (class "Default")
      (node (ref "R6") (pin "1") (pinfunction "1_1") (pintype "passive"))
      (node (ref "R7") (pin "2") (pinfunction "2_2") (pintype "passive"))
      (node (ref "U$15") (pin "12") (pinfunction "12_12") (pintype "passive"))
    )
    (net (code "4") (name "BL_CS") (class "Default")
      (node (ref "M3C1") (pin "1") (pinfunction "1_1") (pintype "passive"))
      (node (ref "M3R8") (pin "1") (pinfunction "1_1") (pintype "passive"))
      (node (ref "U$2") (pin "16") (pinfunction "PA6/SPI1_MISO/ADC12_IN6/TIM3_CH1_16") (pintype "bidirectional"))
    )
    (net (code "5") (name "BL_DIR") (class "Default")
      (node (ref "M3R5") (pin "1") (pinfunction "1_1") (pintype "passive"))
      (node (ref "MU2") (pin "1") (pinfunction "1A_1") (pintype "bidirectional"))
      (node (ref "U$15") (pin "5") (pinfunction "5_5") (pintype "passive"))
    )
    (net (code "6") (name "BL_OUTA") (class "Default")
      (node (ref "M3D1") (pin "C") (pinfunction "C_C") (pintype "passive"))
      (node (ref "M3D2") (pin "A") (pinfunction "A_A") (pintype "passive"))
      (node (ref "M3J1") (pin "+") (pinfunction "P$V+_+") (pintype "bidirectional"))
      (node (ref "M_BL") (pin "P$1") (pinfunction "OUT_A_P$1") (pintype "output"))
      (node (ref "M_BL") (pin "P$2") (pinfunction "OUT_A_P$2") (pintype "output"))
      (node (ref "M_BL") (pin "P$3") (pinfunction "OUT_A_P$3") (pintype "output"))
      (node (ref "M_BL") (pin "P$4") (pinfunction "OUT_A_P$4") (pintype "output"))
      (node (ref "M_BL") (pin "P$5") (pinfunction "OUT_A_P$5") (pintype "output"))
      (node (ref "M_BL") (pin "P$6") (pinfunction "OUT_A_P$6") (pintype "output"))
      (node (ref "M_BL") (pin "P$7") (pinfunction "OUT_A_P$7") (pintype "output"))
      (node (ref "M_BL") (pin "P$8") (pinfunction "OUT_A_P$8") (pintype "output"))
      (node (ref "M_BL") (pin "P$9") (pinfunction "OUT_A_P$9") (pintype "output"))
      (node (ref "M_BL") (pin "P1") (pinfunction "OUT_A_P1") (pintype "output"))
      (node (ref "M_BL") (pin "P25") (pinfunction "OUT_A_P25") (pintype "output"))
      (node (ref "M_BL") (pin "P30") (pinfunction "OUT_A_P30") (pintype "output"))
      (node (ref "M_BL") (pin "SLUG2") (pinfunction "OUT_A_SLUG2") (pintype "output"))
    )
    (net (code "7") (name "BL_OUTB") (class "Default")
      (node (ref "M3J1") (pin "-") (pinfunction "P$V-_-") (pintype "bidirectional"))
      (node (ref "M3R12") (pin "2") (pinfunction "2_2") (pintype "passive"))
      (node (ref "M_BL") (pin "P$10") (pinfunction "OUT_B_P$10") (pintype "output"))
      (node (ref "M_BL") (pin "P$11") (pinfunction "OUT_B_P$11") (pintype "output"))
      (node (ref "M_BL") (pin "P$12") (pinfunction "OUT_B_P$12") (pintype "output"))
      (node (ref "M_BL") (pin "P$13") (pinfunction "OUT_B_P$13") (pintype "output"))
      (node (ref "M_BL") (pin "P$14") (pinfunction "OUT_B_P$14") (pintype "output"))
      (node (ref "M_BL") (pin "P$15") (pinfunction "OUT_B_P$15") (pintype "output"))
      (node (ref "M_BL") (pin "P$16") (pinfunction "OUT_B_P$16") (pintype "output"))
      (node (ref "M_BL") (pin "P$17") (pinfunction "OUT_B_P$17") (pintype "output"))
      (node (ref "M_BL") (pin "P$18") (pinfunction "OUT_B_P$18") (pintype "output"))
      (node (ref "M_BL") (pin "P15") (pinfunction "OUT_B_P15") (pintype "output"))
      (node (ref "M_BL") (pin "P16") (pinfunction "OUT_B_P16") (pintype "output"))
      (node (ref "M_BL") (pin "P21") (pinfunction "OUT_B_P21") (pintype "output"))
      (node (ref "M_BL") (pin "SLUG3") (pinfunction "OUT_B_SLUG3") (pintype "output"))
    )
    (net (code "8") (name "BL_PWM") (class "Default")
      (node (ref "M3R11") (pin "2") (pinfunction "2_2") (pintype "passive"))
      (node (ref "M3R7") (pin "1") (pinfunction "1_1") (pintype "passive"))
      (node (ref "U$15") (pin "6") (pinfunction "6_6") (pintype "passive"))
    )
    (net (code "9") (name "BOOT0") (class "Default")
      (node (ref "BOOT") (pin "P$2") (pinfunction "2_P$2") (pintype "passive"))
      (node (ref "R4") (pin "2") (pinfunction "2_2") (pintype "passive"))
      (node (ref "U$2") (pin "44") (pinfunction "BOOT0_44") (pintype "input"))
      (node (ref "U$2") (pin "45") (pinfunction "PB8/TIM4_CH3_45") (pintype "bidirectional"))
    )
    (net (code "10") (name "BR_CS") (class "Default")
      (node (ref "M4C1") (pin "1") (pinfunction "1_1") (pintype "passive"))
      (node (ref "M4R8") (pin "1") (pinfunction "1_1") (pintype "passive"))
      (node (ref "U$2") (pin "17") (pinfunction "PA7/SPI1_MOSI/ADC12_IN7/TIM3_CH2_17") (pintype "bidirectional"))
    )
    (net (code "11") (name "BR_DIR") (class "Default")
      (node (ref "M4R5") (pin "1") (pinfunction "1_1") (pintype "passive"))
      (node (ref "MU2") (pin "3") (pinfunction "2A_3") (pintype "bidirectional"))
      (node (ref "U$15") (pin "7") (pinfunction "7_7") (pintype "passive"))
    )
    (net (code "12") (name "BR_OUTA") (class "Default")
      (node (ref "M4D1") (pin "C") (pinfunction "C_C") (pintype "passive"))
      (node (ref "M4D2") (pin "A") (pinfunction "A_A") (pintype "passive"))
      (node (ref "M4J1") (pin "+") (pinfunction "P$V+_+") (pintype "bidirectional"))
      (node (ref "M_BR") (pin "P$1") (pinfunction "OUT_A_P$1") (pintype "output"))
      (node (ref "M_BR") (pin "P$2") (pinfunction "OUT_A_P$2") (pintype "output"))
      (node (ref "M_BR") (pin "P$3") (pinfunction "OUT_A_P$3") (pintype "output"))
      (node (ref "M_BR") (pin "P$4") (pinfunction "OUT_A_P$4") (pintype "output"))
      (node (ref "M_BR") (pin "P$5") (pinfunction "OUT_A_P$5") (pintype "output"))
      (node (ref "M_BR") (pin "P$6") (pinfunction "OUT_A_P$6") (pintype "output"))
      (node (ref "M_BR") (pin "P$7") (pinfunction "OUT_A_P$7") (pintype "output"))
      (node (ref "M_BR") (pin "P$8") (pinfunction "OUT_A_P$8") (pintype "output"))
      (node (ref "M_BR") (pin "P$9") (pinfunction "OUT_A_P$9") (pintype "output"))
      (node (ref "M_BR") (pin "P1") (pinfunction "OUT_A_P1") (pintype "output"))
      (node (ref "M_BR") (pin "P25") (pinfunction "OUT_A_P25") (pintype "output"))
      (node (ref "M_BR") (pin "P30") (pinfunction "OUT_A_P30") (pintype "output"))
      (node (ref "M_BR") (pin "SLUG2") (pinfunction "OUT_A_SLUG2") (pintype "output"))
    )
    (net (code "13") (name "BR_OUTB") (class "Default")
      (node (ref "M4J1") (pin "-") (pinfunction "P$V-_-") (pintype "bidirectional"))
      (node (ref "M4R12") (pin "2") (pinfunction "2_2") (pintype "passive"))
      (node (ref "M_BR") (pin "P$10") (pinfunction "OUT_B_P$10") (pintype "output"))
      (node (ref "M_BR") (pin "P$11") (pinfunction "OUT_B_P$11") (pintype "output"))
      (node (ref "M_BR") (pin "P$12") (pinfunction "OUT_B_P$12") (pintype "output"))
      (node (ref "M_BR") (pin "P$13") (pinfunction "OUT_B_P$13") (pintype "output"))
      (node (ref "M_BR") (pin "P$14") (pinfunction "OUT_B_P$14") (pintype "output"))
      (node (ref "M_BR") (pin "P$15") (pinfunction "OUT_B_P$15") (pintype "output"))
      (node (ref "M_BR") (pin "P$16") (pinfunction "OUT_B_P$16") (pintype "output"))
      (node (ref "M_BR") (pin "P$17") (pinfunction "OUT_B_P$17") (pintype "output"))
      (node (ref "M_BR") (pin "P$18") (pinfunction "OUT_B_P$18") (pintype "output"))
      (node (ref "M_BR") (pin "P15") (pinfunction "OUT_B_P15") (pintype "output"))
      (node (ref "M_BR") (pin "P16") (pinfunction "OUT_B_P16") (pintype "output"))
      (node (ref "M_BR") (pin "P21") (pinfunction "OUT_B_P21") (pintype "output"))
      (node (ref "M_BR") (pin "SLUG3") (pinfunction "OUT_B_SLUG3") (pintype "output"))
    )
    (net (code "14") (name "BR_PWM") (class "Default")
      (node (ref "M4R11") (pin "2") (pinfunction "2_2") (pintype "passive"))
      (node (ref "M4R7") (pin "1") (pinfunction "1_1") (pintype "passive"))
      (node (ref "U$15") (pin "8") (pinfunction "8_8") (pintype "passive"))
    )
    (net (code "15") (name "FL_CS") (class "Default")
      (node (ref "M1C1") (pin "1") (pinfunction "1_1") (pintype "passive"))
      (node (ref "M1R8") (pin "1") (pinfunction "1_1") (pintype "passive"))
      (node (ref "U$2") (pin "14") (pinfunction "PA4/SPI1_NSS/USART2_CK/ADC12_IN4_14") (pintype "bidirectional"))
    )
    (net (code "16") (name "FL_DIR") (class "Default")
      (node (ref "M1R5") (pin "1") (pinfunction "1_1") (pintype "passive"))
      (node (ref "MU1") (pin "1") (pinfunction "1A_1") (pintype "bidirectional"))
      (node (ref "U$15") (pin "1") (pinfunction "1_1") (pintype "passive"))
    )
    (net (code "17") (name "FL_OUTA") (class "Default")
      (node (ref "M1D1") (pin "C") (pinfunction "C_C") (pintype "passive"))
      (node (ref "M1D2") (pin "A") (pinfunction "A_A") (pintype "passive"))
      (node (ref "M1J1") (pin "+") (pinfunction "P$V+_+") (pintype "bidirectional"))
      (node (ref "M_FL") (pin "P$1") (pinfunction "OUT_A_P$1") (pintype "output"))
      (node (ref "M_FL") (pin "P$2") (pinfunction "OUT_A_P$2") (pintype "output"))
      (node (ref "M_FL") (pin "P$3") (pinfunction "OUT_A_P$3") (pintype "output"))
      (node (ref "M_FL") (pin "P$4") (pinfunction "OUT_A_P$4") (pintype "output"))
      (node (ref "M_FL") (pin "P$5") (pinfunction "OUT_A_P$5") (pintype "output"))
      (node (ref "M_FL") (pin "P$6") (pinfunction "OUT_A_P$6") (pintype "output"))
      (node (ref "M_FL") (pin "P$7") (pinfunction "OUT_A_P$7") (pintype "output"))
      (node (ref "M_FL") (pin "P$8") (pinfunction "OUT_A_P$8") (pintype "output"))
      (node (ref "M_FL") (pin "P$9") (pinfunction "OUT_A_P$9") (pintype "output"))
      (node (ref "M_FL") (pin "P1") (pinfunction "OUT_A_P1") (pintype "output"))
      (node (ref "M_FL") (pin "P25") (pinfunction "OUT_A_P25") (pintype "output"))
      (node (ref "M_FL") (pin "P30") (pinfunction "OUT_A_P30") (pintype "output"))
      (node (ref "M_FL") (pin "SLUG2") (pinfunction "OUT_A_SLUG2") (pintype "output"))
    )
    (net (code "18") (name "FL_OUTB") (class "Default")
      (node (ref "M1J1") (pin "-") (pinfunction "P$V-_-") (pintype "bidirectional"))
      (node (ref "M1R12") (pin "2") (pinfunction "2_2") (pintype "passive"))
      (node (ref "M_FL") (pin "P$10") (pinfunction "OUT_B_P$10") (pintype "output"))
      (node (ref "M_FL") (pin "P$11") (pinfunction "OUT_B_P$11") (pintype "output"))
      (node (ref "M_FL") (pin "P$12") (pinfunction "OUT_B_P$12") (pintype "output"))
      (node (ref "M_FL") (pin "P$13") (pinfunction "OUT_B_P$13") (pintype "output"))
      (node (ref "M_FL") (pin "P$14") (pinfunction "OUT_B_P$14") (pintype "output"))
      (node (ref "M_FL") (pin "P$15") (pinfunction "OUT_B_P$15") (pintype "output"))
      (node (ref "M_FL") (pin "P$16") (pinfunction "OUT_B_P$16") (pintype "output"))
      (node (ref "M_FL") (pin "P$17") (pinfunction "OUT_B_P$17") (pintype "output"))
      (node (ref "M_FL") (pin "P$18") (pinfunction "OUT_B_P$18") (pintype "output"))
      (node (ref "M_FL") (pin "P15") (pinfunction "OUT_B_P15") (pintype "output"))
      (node (ref "M_FL") (pin "P16") (pinfunction "OUT_B_P16") (pintype "output"))
      (node (ref "M_FL") (pin "P21") (pinfunction "OUT_B_P21") (pintype "output"))
      (node (ref "M_FL") (pin "SLUG3") (pinfunction "OUT_B_SLUG3") (pintype "output"))
    )
    (net (code "19") (name "FL_PWM") (class "Default")
      (node (ref "M1R11") (pin "2") (pinfunction "2_2") (pintype "passive"))
      (node (ref "M1R7") (pin "1") (pinfunction "1_1") (pintype "passive"))
      (node (ref "U$15") (pin "2") (pinfunction "2_2") (pintype "passive"))
    )
    (net (code "20") (name "FR_CS") (class "Default")
      (node (ref "M2C1") (pin "1") (pinfunction "1_1") (pintype "passive"))
      (node (ref "M2R8") (pin "1") (pinfunction "1_1") (pintype "passive"))
      (node (ref "U$2") (pin "15") (pinfunction "PA5/SPI1_SCK/ADC12_IN5_15") (pintype "bidirectional"))
    )
    (net (code "21") (name "FR_DIR") (class "Default")
      (node (ref "M2R5") (pin "1") (pinfunction "1_1") (pintype "passive"))
      (node (ref "MU1") (pin "3") (pinfunction "2A_3") (pintype "bidirectional"))
      (node (ref "U$15") (pin "3") (pinfunction "3_3") (pintype "passive"))
    )
    (net (code "22") (name "FR_OUTA") (class "Default")
      (node (ref "M2D1") (pin "C") (pinfunction "C_C") (pintype "passive"))
      (node (ref "M2D2") (pin "A") (pinfunction "A_A") (pintype "passive"))
      (node (ref "M2J1") (pin "+") (pinfunction "P$V+_+") (pintype "bidirectional"))
      (node (ref "M_FR") (pin "P$1") (pinfunction "OUT_A_P$1") (pintype "output"))
      (node (ref "M_FR") (pin "P$2") (pinfunction "OUT_A_P$2") (pintype "output"))
      (node (ref "M_FR") (pin "P$3") (pinfunction "OUT_A_P$3") (pintype "output"))
      (node (ref "M_FR") (pin "P$4") (pinfunction "OUT_A_P$4") (pintype "output"))
      (node (ref "M_FR") (pin "P$5") (pinfunction "OUT_A_P$5") (pintype "output"))
      (node (ref "M_FR") (pin "P$6") (pinfunction "OUT_A_P$6") (pintype "output"))
      (node (ref "M_FR") (pin "P$7") (pinfunction "OUT_A_P$7") (pintype "output"))
      (node (ref "M_FR") (pin "P$8") (pinfunction "OUT_A_P$8") (pintype "output"))
      (node (ref "M_FR") (pin "P$9") (pinfunction "OUT_A_P$9") (pintype "output"))
      (node (ref "M_FR") (pin "P1") (pinfunction "OUT_A_P1") (pintype "output"))
      (node (ref "M_FR") (pin "P25") (pinfunction "OUT_A_P25") (pintype "output"))
      (node (ref "M_FR") (pin "P30") (pinfunction "OUT_A_P30") (pintype "output"))
      (node (ref "M_FR") (pin "SLUG2") (pinfunction "OUT_A_SLUG2") (pintype "output"))
    )
    (net (code "23") (name "FR_OUTB") (class "Default")
      (node (ref "M2J1") (pin "-") (pinfunction "P$V-_-") (pintype "bidirectional"))
      (node (ref "M2R12") (pin "2") (pinfunction "2_2") (pintype "passive"))
      (node (ref "M_FR") (pin "P$10") (pinfunction "OUT_B_P$10") (pintype "output"))
      (node (ref "M_FR") (pin "P$11") (pinfunction "OUT_B_P$11") (pintype "output"))
      (node (ref "M_FR") (pin "P$12") (pinfunction "OUT_B_P$12") (pintype "output"))
      (node (ref "M_FR") (pin "P$13") (pinfunction "OUT_B_P$13") (pintype "output"))
      (node (ref "M_FR") (pin "P$14") (pinfunction "OUT_B_P$14") (pintype "output"))
      (node (ref "M_FR") (pin "P$15") (pinfunction "OUT_B_P$15") (pintype "output"))
      (node (ref "M_FR") (pin "P$16") (pinfunction "OUT_B_P$16") (pintype "output"))
      (node (ref "M_FR") (pin "P$17") (pinfunction "OUT_B_P$17") (pintype "output"))
      (node (ref "M_FR") (pin "P$18") (pinfunction "OUT_B_P$18") (pintype "output"))
      (node (ref "M_FR") (pin "P15") (pinfunction "OUT_B_P15") (pintype "output"))
      (node (ref "M_FR") (pin "P16") (pinfunction "OUT_B_P16") (pintype "output"))
      (node (ref "M_FR") (pin "P21") (pinfunction "OUT_B_P21") (pintype "output"))
      (node (ref "M_FR") (pin "SLUG3") (pinfunction "OUT_B_SLUG3") (pintype "output"))
    )
    (net (code "24") (name "FR_PWM") (class "Default")
      (node (ref "M2R11") (pin "2") (pinfunction "2_2") (pintype "passive"))
      (node (ref "M2R7") (pin "1") (pinfunction "1_1") (pintype "passive"))
      (node (ref "U$15") (pin "4") (pinfunction "4_4") (pintype "passive"))
    )
    (net (code "25") (name "GND") (class "Default")
      (node (ref "1C1") (pin "2") (pinfunction "2_2") (pintype "passive"))
      (node (ref "1C2") (pin "2") (pinfunction "2_2") (pintype "passive"))
      (node (ref "1C4") (pin "C") (pinfunction "-_C") (pintype "passive"))
      (node (ref "1C5") (pin "2") (pinfunction "2_2") (pintype "passive"))
      (node (ref "1D1") (pin "A") (pinfunction "A_A") (pintype "passive"))
      (node (ref "1R2") (pin "1") (pinfunction "1_1") (pintype "passive"))
      (node (ref "2C1") (pin "2") (pinfunction "2_2") (pintype "passive"))
      (node (ref "2C2") (pin "2") (pinfunction "2_2") (pintype "passive"))
      (node (ref "2C3") (pin "2") (pinfunction "2_2") (pintype "passive"))
      (node (ref "2R1") (pin "1") (pinfunction "1_1") (pintype "passive"))
      (node (ref "2R2") (pin "1") (pinfunction "1_1") (pintype "passive"))
      (node (ref "2R3") (pin "1") (pinfunction "1_1") (pintype "passive"))
      (node (ref "3C1") (pin "2") (pinfunction "2_2") (pintype "passive"))
      (node (ref "3C2") (pin "2") (pinfunction "2_2") (pintype "passive"))
      (node (ref "C1") (pin "2") (pinfunction "2_2") (pintype "passive"))
      (node (ref "C2") (pin "2") (pinfunction "2_2") (pintype "passive"))
      (node (ref "C3") (pin "2") (pinfunction "2_2") (pintype "passive"))
      (node (ref "C6") (pin "1") (pinfunction "1_1") (pintype "passive"))
      (node (ref "C7") (pin "1") (pinfunction "1_1") (pintype "passive"))
      (node (ref "C8") (pin "2") (pinfunction "2_2") (pintype "passive"))
      (node (ref "D1") (pin "C") (pinfunction "C_C") (pintype "passive"))
      (node (ref "FB2") (pin "1") (pinfunction "1_1") (pintype "passive"))
      (node (ref "GND_M1B") (pin "P$1") (pinfunction "1_P$1") (pintype "passive"))
      (node (ref "GND_M2B") (pin "P$1") (pinfunction "1_P$1") (pintype "passive"))
      (node (ref "GND_M3B") (pin "P$1") (pinfunction "1_P$1") (pintype "passive"))
      (node (ref "GND_M4B") (pin "P$1") (pinfunction "1_P$1") (pintype "passive"))
      (node (ref "LC1") (pin "2") (pinfunction "2_2") (pintype "passive"))
      (node (ref "LC2") (pin "2") (pinfunction "2_2") (pintype "passive"))
      (node (ref "LC3") (pin "2") (pinfunction "2_2") (pintype "passive"))
      (node (ref "LC4") (pin "2") (pinfunction "2_2") (pintype "passive"))
      (node (ref "LC5") (pin "2") (pinfunction "2_2") (pintype "passive"))
      (node (ref "LC6") (pin "2") (pinfunction "2_2") (pintype "passive"))
      (node (ref "LED") (pin "1") (pinfunction "1_1") (pintype "passive"))
      (node (ref "LG_R2") (pin "1") (pinfunction "1_1") (pintype "passive"))
      (node (ref "LR1") (pin "2") (pinfunction "2_2") (pintype "passive"))
      (node (ref "M1C1") (pin "2") (pinfunction "2_2") (pintype "passive"))
      (node (ref "M1R10") (pin "1") (pinfunction "1_1") (pintype "passive"))
      (node (ref "M1R11") (pin "1") (pinfunction "1_1") (pintype "passive"))
      (node (ref "M1R9") (pin "1") (pinfunction "1_1") (pintype "passive"))
      (node (ref "M2C1") (pin "2") (pinfunction "2_2") (pintype "passive"))
      (node (ref "M2R10") (pin "1") (pinfunction "1_1") (pintype "passive"))
      (node (ref "M2R11") (pin "1") (pinfunction "1_1") (pintype "passive"))
      (node (ref "M2R9") (pin "1") (pinfunction "1_1") (pintype "passive"))
      (node (ref "M3C1") (pin "2") (pinfunction "2_2") (pintype "passive"))
      (node (ref "M3R10") (pin "1") (pinfunction "1_1") (pintype "passive"))
      (node (ref "M3R11") (pin "1") (pinfunction "1_1") (pintype "passive"))
      (node (ref "M3R9") (pin "1") (pinfunction "1_1") (pintype "passive"))
      (node (ref "M4C1") (pin "2") (pinfunction "2_2") (pintype "passive"))
      (node (ref "M4R10") (pin "1") (pinfunction "1_1") (pintype "passive"))
      (node (ref "M4R11") (pin "1") (pinfunction "1_1") (pintype "passive"))
      (node (ref "M4R9") (pin "1") (pinfunction "1_1") (pintype "passive"))
      (node (ref "MOUSE") (pin "2") (pinfunction "2_2") (pintype "passive"))
      (node (ref "MU1") (pin "2") (pinfunction "GND_2") (pintype "bidirectional"))
      (node (ref "MU2") (pin "2") (pinfunction "GND_2") (pintype "bidirectional"))
      (node (ref "MUX_L1") (pin "12") (pinfunction "GND_12") (pintype "bidirectional"))
      (node (ref "MUX_L2") (pin "12") (pinfunction "GND_12") (pintype "bidirectional"))
      (node (ref "MUX_L3") (pin "12") (pinfunction "GND_12") (pintype "bidirectional"))
      (node (ref "R2") (pin "1") (pinfunction "1_1") (pintype "passive"))
      (node (ref "R4") (pin "1") (pinfunction "1_1") (pintype "passive"))
      (node (ref "R7") (pin "1") (pinfunction "1_1") (pintype "passive"))
      (node (ref "S3") (pin "1") (pinfunction "O_1") (pintype "passive"))
      (node (ref "U$1") (pin "-") (pinfunction "P$V-_-") (pintype "bidirectional"))
      (node (ref "U$15") (pin "14") (pinfunction "14_14") (pintype "passive"))
      (node (ref "U$2") (pin "23") (pinfunction "VSS_1_23") (pintype "power_in"))
      (node (ref "U$2") (pin "35") (pinfunction "VSS_2_35") (pintype "power_in"))
      (node (ref "U$2") (pin "47") (pinfunction "VSS_3_47") (pintype "power_in"))
      (node (ref "U1") (pin "6") (pinfunction "GND_6") (pintype "power_in"))
      (node (ref "U1") (pin "9") (pinfunction "GND_9") (pintype "power_in"))
      (node (ref "U1") (pin "P$1") (pinfunction "GND_P$1") (pintype "power_in"))
      (node (ref "U1") (pin "P$2") (pinfunction "GND_P$2") (pintype "power_in"))
      (node (ref "U1") (pin "P$3") (pinfunction "GND_P$3") (pintype "power_in"))
      (node (ref "U1") (pin "P$4") (pinfunction "GND_P$4") (pintype "power_in"))
      (node (ref "U1") (pin "P$5") (pinfunction "GND_P$5") (pintype "power_in"))
      (node (ref "U1") (pin "P$6") (pinfunction "GND_P$6") (pintype "power_in"))
      (node (ref "X2") (pin "1") (pinfunction "1_1") (pintype "passive"))
    )
    (net (code "26") (name "GND_M") (class "Default")
      (node (ref "GND_M1A") (pin "P$1") (pinfunction "1_P$1") (pintype "passive"))
      (node (ref "GND_M2A") (pin "P$1") (pinfunction "1_P$1") (pintype "passive"))
      (node (ref "GND_M3A") (pin "P$1") (pinfunction "1_P$1") (pintype "passive"))
      (node (ref "GND_M4A") (pin "P$1") (pinfunction "1_P$1") (pintype "passive"))
      (node (ref "M1C2") (pin "2") (pinfunction "-_2") (pintype "passive"))
      (node (ref "M1C3") (pin "2") (pinfunction "2_2") (pintype "passive"))
      (node (ref "M2C2") (pin "2") (pinfunction "-_2") (pintype "passive"))
      (node (ref "M2C3") (pin "2") (pinfunction "2_2") (pintype "passive"))
      (node (ref "M3C2") (pin "2") (pinfunction "-_2") (pintype "passive"))
      (node (ref "M3C3") (pin "2") (pinfunction "2_2") (pintype "passive"))
      (node (ref "M4C2") (pin "2") (pinfunction "-_2") (pintype "passive"))
      (node (ref "M4C3") (pin "2") (pinfunction "2_2") (pintype "passive"))
      (node (ref "M_BL") (pin "P18") (pinfunction "GND_P18") (pintype "output"))
      (node (ref "M_BL") (pin "P19") (pinfunction "GND_P19") (pintype "output"))
      (node (ref "M_BL") (pin "P20") (pinfunction "GND_P20") (pintype "output"))
      (node (ref "M_BL") (pin "P26") (pinfunction "GND_P26") (pintype "output"))
      (node (ref "M_BL") (pin "P27") (pinfunction "GND_P27") (pintype "output"))
      (node (ref "M_BL") (pin "P28") (pinfunction "GND_P28") (pintype "output"))
      (node (ref "M_BR") (pin "P18") (pinfunction "GND_P18") (pintype "output"))
      (node (ref "M_BR") (pin "P19") (pinfunction "GND_P19") (pintype "output"))
      (node (ref "M_BR") (pin "P20") (pinfunction "GND_P20") (pintype "output"))
      (node (ref "M_BR") (pin "P26") (pinfunction "GND_P26") (pintype "output"))
      (node (ref "M_BR") (pin "P27") (pinfunction "GND_P27") (pintype "output"))
      (node (ref "M_BR") (pin "P28") (pinfunction "GND_P28") (pintype "output"))
      (node (ref "M_FL") (pin "P18") (pinfunction "GND_P18") (pintype "output"))
      (node (ref "M_FL") (pin "P19") (pinfunction "GND_P19") (pintype "output"))
      (node (ref "M_FL") (pin "P20") (pinfunction "GND_P20") (pintype "output"))
      (node (ref "M_FL") (pin "P26") (pinfunction "GND_P26") (pintype "output"))
      (node (ref "M_FL") (pin "P27") (pinfunction "GND_P27") (pintype "output"))
      (node (ref "M_FL") (pin "P28") (pinfunction "GND_P28") (pintype "output"))
      (node (ref "M_FR") (pin "P18") (pinfunction "GND_P18") (pintype "output"))
      (node (ref "M_FR") (pin "P19") (pinfunction "GND_P19") (pintype "output"))
      (node (ref "M_FR") (pin "P20") (pinfunction "GND_P20") (pintype "output"))
      (node (ref "M_FR") (pin "P26") (pinfunction "GND_P26") (pintype "output"))
      (node (ref "M_FR") (pin "P27") (pinfunction "GND_P27") (pintype "output"))
      (node (ref "M_FR") (pin "P28") (pinfunction "GND_P28") (pintype "output"))
    )
    (net (code "27") (name "LG_SIG") (class "Default")
      (node (ref "LDR") (pin "2") (pinfunction "2_2") (pintype "passive"))
      (node (ref "LG_R2") (pin "2") (pinfunction "2_2") (pintype "passive"))
      (node (ref "U$2") (pin "13") (pinfunction "PA3/USART2_RX/ADC12_IN3/TIM2_CH4_13") (pintype "bidirectional"))
    )
    (net (code "28") (name "LIGHT_INT") (class "Default")
      (node (ref "U$15") (pin "10") (pinfunction "10_10") (pintype "passive"))
      (node (ref "U$2") (pin "29") (pinfunction "PA8/USART1_CK/TIM1_CH1/MCO_29") (pintype "bidirectional"))
    )
    (net (code "29") (name "LS0") (class "Default")
      (node (ref "MUX_L1") (pin "10") (pinfunction "S0_10") (pintype "input"))
      (node (ref "MUX_L2") (pin "10") (pinfunction "S0_10") (pintype "input"))
      (node (ref "MUX_L3") (pin "10") (pinfunction "S0_10") (pintype "input"))
      (node (ref "U$2") (pin "25") (pinfunction "PB12/SPI2_NSS/I2C2_SMBA/USART3_CK/TIM1_BKIN_25") (pintype "input"))
    )
    (net (code "30") (name "LS1") (class "Default")
      (node (ref "MUX_L1") (pin "11") (pinfunction "S1_11") (pintype "input"))
      (node (ref "MUX_L2") (pin "11") (pinfunction "S1_11") (pintype "input"))
      (node (ref "MUX_L3") (pin "11") (pinfunction "S1_11") (pintype "input"))
      (node (ref "U$2") (pin "26") (pinfunction "PB13/SPI2_SCK/USART3_CTS/TIM1_CH1N_26") (pintype "input"))
    )
    (net (code "31") (name "LS2") (class "Default")
      (node (ref "MUX_L1") (pin "14") (pinfunction "S2_14") (pintype "input"))
      (node (ref "MUX_L2") (pin "14") (pinfunction "S2_14") (pintype "input"))
      (node (ref "MUX_L3") (pin "14") (pinfunction "S2_14") (pintype "input"))
      (node (ref "U$2") (pin "27") (pinfunction "PB14/SPI2_MISO/USART3_RTS/TIM1_CH2N_27") (pintype "input"))
    )
    (net (code "32") (name "LS3") (class "Default")
      (node (ref "MUX_L1") (pin "13") (pinfunction "S3_13") (pintype "input"))
      (node (ref "MUX_L2") (pin "13") (pinfunction "S3_13") (pintype "input"))
      (node (ref "MUX_L3") (pin "13") (pinfunction "S3_13") (pintype "input"))
      (node (ref "U$2") (pin "28") (pinfunction "PB15/SPI2_MOSI/TIM1_CH3N_28") (pintype "input"))
    )
    (net (code "33") (name "LSIG1") (class "Default")
      (node (ref "2C4") (pin "1") (pinfunction "1_1") (pintype "passive"))
      (node (ref "2R4") (pin "2") (pinfunction "2_2") (pintype "passive"))
      (node (ref "MUX_L1") (pin "1") (pinfunction "COM_1") (pintype "bidirectional"))
      (node (ref "U$2") (pin "10") (pinfunction "PA0_WKUP/USART2_CTS/ADC12_IN0/TIM2_CH1_ETR_10") (pintype "bidirectional"))
    )
    (net (code "34") (name "LSIG2") (class "Default")
      (node (ref "2C5") (pin "1") (pinfunction "1_1") (pintype "passive"))
      (node (ref "2R5") (pin "2") (pinfunction "2_2") (pintype "passive"))
      (node (ref "MUX_L2") (pin "1") (pinfunction "COM_1") (pintype "bidirectional"))
      (node (ref "U$2") (pin "11") (pinfunction "PA1/USART2_RTS/ADC12_IN1/TIM2_CH2_11") (pintype "bidirectional"))
    )
    (net (code "35") (name "LSIG3") (class "Default")
      (node (ref "2C6") (pin "1") (pinfunction "1_1") (pintype "passive"))
      (node (ref "2R6") (pin "2") (pinfunction "2_2") (pintype "passive"))
      (node (ref "MUX_L3") (pin "1") (pinfunction "COM_1") (pintype "bidirectional"))
      (node (ref "U$2") (pin "12") (pinfunction "PA2/USART2_TX/ADC12_IN2/TIM2_CH3_12") (pintype "bidirectional"))
    )
    (net (code "36") (name "LSWITCH") (class "Default")
      (node (ref "LC1") (pin "1") (pinfunction "1_1") (pintype "passive"))
      (node (ref "LC2") (pin "1") (pinfunction "1_1") (pintype "passive"))
      (node (ref "LC3") (pin "1") (pinfunction "1_1") (pintype "passive"))
      (node (ref "LC4") (pin "1") (pinfunction "1_1") (pintype "passive"))
      (node (ref "LC5") (pin "1") (pinfunction "1_1") (pintype "passive"))
      (node (ref "LC6") (pin "1") (pinfunction "1_1") (pintype "passive"))
      (node (ref "LD1") (pin "A") (pinfunction "A_A") (pintype "passive"))
      (node (ref "LD10") (pin "A") (pinfunction "A_A") (pintype "passive"))
      (node (ref "LD11") (pin "A") (pinfunction "A_A") (pintype "passive"))
      (node (ref "LD12") (pin "A") (pinfunction "A_A") (pintype "passive"))
      (node (ref "LD13") (pin "A") (pinfunction "A_A") (pintype "passive"))
      (node (ref "LD14") (pin "A") (pinfunction "A_A") (pintype "passive"))
      (node (ref "LD15") (pin "A") (pinfunction "A_A") (pintype "passive"))
      (node (ref "LD16") (pin "A") (pinfunction "A_A") (pintype "passive"))
      (node (ref "LD17") (pin "A") (pinfunction "A_A") (pintype "passive"))
      (node (ref "LD18") (pin "A") (pinfunction "A_A") (pintype "passive"))
      (node (ref "LD19") (pin "A") (pinfunction "A_A") (pintype "passive"))
      (node (ref "LD2") (pin "A") (pinfunction "A_A") (pintype "passive"))
      (node (ref "LD20") (pin "A") (pinfunction "A_A") (pintype "passive"))
      (node (ref "LD21") (pin "A") (pinfunction "A_A") (pintype "passive"))
      (node (ref "LD22") (pin "A") (pinfunction "A_A") (pintype "passive"))
      (node (ref "LD23") (pin "A") (pinfunction "A_A") (pintype "passive"))
      (node (ref "LD24") (pin "A") (pinfunction "A_A") (pintype "passive"))
      (node (ref "LD25") (pin "A") (pinfunction "A_A") (pintype "passive"))
      (node (ref "LD26") (pin "A") (pinfunction "A_A") (pintype "passive"))
      (node (ref "LD27") (pin "A") (pinfunction "A_A") (pintype "passive"))
      (node (ref "LD28") (pin "A") (pinfunction "A_A") (pintype "passive"))
      (node (ref "LD29") (pin "A") (pinfunction "A_A") (pintype "passive"))
      (node (ref "LD3") (pin "A") (pinfunction "A_A") (pintype "passive"))
      (node (ref "LD30") (pin "A") (pinfunction "A_A") (pintype "passive"))
      (node (ref "LD31") (pin "A") (pinfunction "A_A") (pintype "passive"))
      (node (ref "LD32") (pin "A") (pinfunction "A_A") (pintype "passive"))
      (node (ref "LD33") (pin "A") (pinfunction "A_A") (pintype "passive"))
      (node (ref "LD34") (pin "A") (pinfunction "A_A") (pintype "passive"))
      (node (ref "LD35") (pin "A") (pinfunction "A_A") (pintype "passive"))
      (node (ref "LD36") (pin "A") (pinfunction "A_A") (pintype "passive"))
      (node (ref "LD4") (pin "A") (pinfunction "A_A") (pintype "passive"))
      (node (ref "LD5") (pin "A") (pinfunction "A_A") (pintype "passive"))
      (node (ref "LD6") (pin "A") (pinfunction "A_A") (pintype "passive"))
      (node (ref "LD7") (pin "A") (pinfunction "A_A") (pintype "passive"))
      (node (ref "LD8") (pin "A") (pinfunction "A_A") (pintype "passive"))
      (node (ref "LD9") (pin "A") (pinfunction "A_A") (pintype "passive"))
      (node (ref "LED") (pin "2") (pinfunction "2_2") (pintype "passive"))
      (node (ref "LS1") (pin "1") (pinfunction "O_1") (pintype "passive"))
    )
    (net (code "37") (name "MISO") (class "Default")
      (node (ref "MOUSE") (pin "7") (pinfunction "7_7") (pintype "passive"))
      (node (ref "U$2") (pin "40") (pinfunction "PB4/NJTRST_40") (pintype "bidirectional"))
    )
    (net (code "38") (name "MOSI") (class "Default")
      (node (ref "MOUSE") (pin "8") (pinfunction "8_8") (pintype "passive"))
      (node (ref "U$2") (pin "41") (pinfunction "PB5/I2C1_SMBA_41") (pintype "input"))
    )
    (net (code "39") (name "MOT") (class "Default")
      (node (ref "MOUSE") (pin "4") (pinfunction "4_4") (pintype "passive"))
      (node (ref "U$2") (pin "43") (pinfunction "PB7/I2C1_SDA/TIM4_CH2_43") (pintype "bidirectional"))
    )
    (net (code "40") (name "M_SWITCH") (class "Default")
      (node (ref "M1R1") (pin "1") (pinfunction "1_1") (pintype "passive"))
      (node (ref "M1R2") (pin "1") (pinfunction "1_1") (pintype "passive"))
      (node (ref "M2R1") (pin "1") (pinfunction "1_1") (pintype "passive"))
      (node (ref "M2R2") (pin "1") (pinfunction "1_1") (pintype "passive"))
      (node (ref "M3R1") (pin "1") (pinfunction "1_1") (pintype "passive"))
      (node (ref "M3R2") (pin "1") (pinfunction "1_1") (pintype "passive"))
      (node (ref "M4R1") (pin "1") (pinfunction "1_1") (pintype "passive"))
      (node (ref "M4R2") (pin "1") (pinfunction "1_1") (pintype "passive"))
      (node (ref "S3") (pin "2") (pinfunction "P_2") (pintype "passive"))
    )
    (net (code "41") (name "NOT_BL_DIR") (class "Default")
      (node (ref "M3R6") (pin "1") (pinfunction "1_1") (pintype "passive"))
      (node (ref "MU2") (pin "6") (pinfunction "1Y_6") (pintype "bidirectional"))
    )
    (net (code "42") (name "NOT_BR_DIR") (class "Default")
      (node (ref "M4R6") (pin "1") (pinfunction "1_1") (pintype "passive"))
      (node (ref "MU2") (pin "4") (pinfunction "2Y_4") (pintype "bidirectional"))
    )
    (net (code "43") (name "NOT_FL_DIR") (class "Default")
      (node (ref "M1R6") (pin "1") (pinfunction "1_1") (pintype "passive"))
      (node (ref "MU1") (pin "6") (pinfunction "1Y_6") (pintype "bidirectional"))
    )
    (net (code "44") (name "NOT_FR_DIR") (class "Default")
      (node (ref "M2R6") (pin "1") (pinfunction "1_1") (pintype "passive"))
      (node (ref "MU1") (pin "4") (pinfunction "2Y_4") (pintype "bidirectional"))
    )
    (net (code "45") (name "NRESET") (class "Default")
      (node (ref "MOUSE") (pin "3") (pinfunction "3_3") (pintype "passive"))
      (node (ref "U$2") (pin "42") (pinfunction "PB6/I2C1_SCL/TIM4_CH1_42") (pintype "input"))
    )
    (net (code "46") (name "Net-(1L1-1)") (class "Default")
      (node (ref "1C3") (pin "2") (pinfunction "2_2") (pintype "passive"))
      (node (ref "1D1") (pin "C") (pinfunction "C_C") (pintype "passive"))
      (node (ref "1L1") (pin "P1") (pinfunction "1_P1") (pintype "passive"))
      (node (ref "U1") (pin "8") (pinfunction "PH_8") (pintype "output"))
    )
    (net (code "47") (name "Net-(BOOT-1)") (class "Default")
      (node (ref "BOOT") (pin "P$1") (pinfunction "1_P$1") (pintype "passive"))
      (node (ref "R3") (pin "1") (pinfunction "1_1") (pintype "passive"))
    )
    (net (code "48") (name "Net-(D1-PadA)") (class "Default")
      (node (ref "D1") (pin "A") (pinfunction "A_A") (pintype "passive"))
      (node (ref "R5") (pin "1") (pinfunction "1_1") (pintype "passive"))
    )
    (net (code "49") (name "Net-(LD1-PadC)") (class "Default")
      (node (ref "LD1") (pin "C") (pinfunction "C_C") (pintype "passive"))
      (node (ref "LD10") (pin "C") (pinfunction "C_C") (pintype "passive"))
      (node (ref "LD11") (pin "C") (pinfunction "C_C") (pintype "passive"))
      (node (ref "LD12") (pin "C") (pinfunction "C_C") (pintype "passive"))
      (node (ref "LD13") (pin "C") (pinfunction "C_C") (pintype "passive"))
      (node (ref "LD14") (pin "C") (pinfunction "C_C") (pintype "passive"))
      (node (ref "LD15") (pin "C") (pinfunction "C_C") (pintype "passive"))
      (node (ref "LD16") (pin "C") (pinfunction "C_C") (pintype "passive"))
      (node (ref "LD17") (pin "C") (pinfunction "C_C") (pintype "passive"))
      (node (ref "LD18") (pin "C") (pinfunction "C_C") (pintype "passive"))
      (node (ref "LD19") (pin "C") (pinfunction "C_C") (pintype "passive"))
      (node (ref "LD2") (pin "C") (pinfunction "C_C") (pintype "passive"))
      (node (ref "LD20") (pin "C") (pinfunction "C_C") (pintype "passive"))
      (node (ref "LD21") (pin "C") (pinfunction "C_C") (pintype "passive"))
      (node (ref "LD22") (pin "C") (pinfunction "C_C") (pintype "passive"))
      (node (ref "LD23") (pin "C") (pinfunction "C_C") (pintype "passive"))
      (node (ref "LD24") (pin "C") (pinfunction "C_C") (pintype "passive"))
      (node (ref "LD25") (pin "C") (pinfunction "C_C") (pintype "passive"))
      (node (ref "LD26") (pin "C") (pinfunction "C_C") (pintype "passive"))
      (node (ref "LD27") (pin "C") (pinfunction "C_C") (pintype "passive"))
      (node (ref "LD28") (pin "C") (pinfunction "C_C") (pintype "passive"))
      (node (ref "LD29") (pin "C") (pinfunction "C_C") (pintype "passive"))
      (node (ref "LD3") (pin "C") (pinfunction "C_C") (pintype "passive"))
      (node (ref "LD30") (pin "C") (pinfunction "C_C") (pintype "passive"))
      (node (ref "LD31") (pin "C") (pinfunction "C_C") (pintype "passive"))
      (node (ref "LD32") (pin "C") (pinfunction "C_C") (pintype "passive"))
      (node (ref "LD33") (pin "C") (pinfunction "C_C") (pintype "passive"))
      (node (ref "LD34") (pin "C") (pinfunction "C_C") (pintype "passive"))
      (node (ref "LD35") (pin "C") (pinfunction "C_C") (pintype "passive"))
      (node (ref "LD36") (pin "C") (pinfunction "C_C") (pintype "passive"))
      (node (ref "LD4") (pin "C") (pinfunction "C_C") (pintype "passive"))
      (node (ref "LD5") (pin "C") (pinfunction "C_C") (pintype "passive"))
      (node (ref "LD6") (pin "C") (pinfunction "C_C") (pintype "passive"))
      (node (ref "LD7") (pin "C") (pinfunction "C_C") (pintype "passive"))
      (node (ref "LD8") (pin "C") (pinfunction "C_C") (pintype "passive"))
      (node (ref "LD9") (pin "C") (pinfunction "C_C") (pintype "passive"))
      (node (ref "LR1") (pin "1") (pinfunction "1_1") (pintype "passive"))
    )
    (net (code "50") (name "Net-(M1C2-+)") (class "Default")
      (node (ref "M1C2") (pin "1") (pinfunction "+_1") (pintype "passive"))
      (node (ref "M1C3") (pin "1") (pinfunction "1_1") (pintype "passive"))
      (node (ref "M1Q1") (pin "4") (pinfunction "D_4") (pintype "bidirectional"))
      (node (ref "M_FL") (pin "P$19") (pinfunction "VCC_P$19") (pintype "power_in"))
      (node (ref "M_FL") (pin "P$20") (pinfunction "VCC_P$20") (pintype "power_in"))
      (node (ref "M_FL") (pin "P$21") (pinfunction "VCC_P$21") (pintype "power_in"))
      (node (ref "M_FL") (pin "P$22") (pinfunction "VCC_P$22") (pintype "power_in"))
      (node (ref "M_FL") (pin "P$23") (pinfunction "VCC_P$23") (pintype "power_in"))
      (node (ref "M_FL") (pin "P$24") (pinfunction "VCC_P$24") (pintype "power_in"))
      (node (ref "M_FL") (pin "P$25") (pinfunction "VCC_P$25") (pintype "power_in"))
      (node (ref "M_FL") (pin "P$26") (pinfunction "VCC_P$26") (pintype "power_in"))
      (node (ref "M_FL") (pin "P$27") (pinfunction "VCC_P$27") (pintype "power_in"))
      (node (ref "M_FL") (pin "P$28") (pinfunction "VCC_P$28") (pintype "power_in"))
      (node (ref "M_FL") (pin "P13") (pinfunction "VCC_P13") (pintype "power_in"))
      (node (ref "M_FL") (pin "P23") (pinfunction "VCC_P23") (pintype "power_in"))
      (node (ref "M_FL") (pin "P3") (pinfunction "VCC_P3") (pintype "power_in"))
      (node (ref "M_FL") (pin "SLUG1") (pinfunction "VCC_SLUG1") (pintype "power_in"))
    )
    (net (code "51") (name "Net-(M1D1-PadA)") (class "Default")
      (node (ref "M1D1") (pin "A") (pinfunction "A_A") (pintype "passive"))
      (node (ref "M1D2") (pin "C") (pinfunction "C_C") (pintype "passive"))
      (node (ref "M1R12") (pin "1") (pinfunction "1_1") (pintype "passive"))
    )
    (net (code "52") (name "Net-(M1Q1-G)") (class "Default")
      (node (ref "M1Q1") (pin "1") (pinfunction "G_1") (pintype "bidirectional"))
      (node (ref "M_FL") (pin "P11") (pinfunction "CP_P11") (pintype "output"))
    )
    (net (code "53") (name "Net-(M2C2-+)") (class "Default")
      (node (ref "M2C2") (pin "1") (pinfunction "+_1") (pintype "passive"))
      (node (ref "M2C3") (pin "1") (pinfunction "1_1") (pintype "passive"))
      (node (ref "M2Q1") (pin "4") (pinfunction "D_4") (pintype "bidirectional"))
      (node (ref "M_FR") (pin "P$19") (pinfunction "VCC_P$19") (pintype "power_in"))
      (node (ref "M_FR") (pin "P$20") (pinfunction "VCC_P$20") (pintype "power_in"))
      (node (ref "M_FR") (pin "P$21") (pinfunction "VCC_P$21") (pintype "power_in"))
      (node (ref "M_FR") (pin "P$22") (pinfunction "VCC_P$22") (pintype "power_in"))
      (node (ref "M_FR") (pin "P$23") (pinfunction "VCC_P$23") (pintype "power_in"))
      (node (ref "M_FR") (pin "P$24") (pinfunction "VCC_P$24") (pintype "power_in"))
      (node (ref "M_FR") (pin "P$25") (pinfunction "VCC_P$25") (pintype "power_in"))
      (node (ref "M_FR") (pin "P$26") (pinfunction "VCC_P$26") (pintype "power_in"))
      (node (ref "M_FR") (pin "P$27") (pinfunction "VCC_P$27") (pintype "power_in"))
      (node (ref "M_FR") (pin "P$28") (pinfunction "VCC_P$28") (pintype "power_in"))
      (node (ref "M_FR") (pin "P13") (pinfunction "VCC_P13") (pintype "power_in"))
      (node (ref "M_FR") (pin "P23") (pinfunction "VCC_P23") (pintype "power_in"))
      (node (ref "M_FR") (pin "P3") (pinfunction "VCC_P3") (pintype "power_in"))
      (node (ref "M_FR") (pin "SLUG1") (pinfunction "VCC_SLUG1") (pintype "power_in"))
    )
    (net (code "54") (name "Net-(M2D1-PadA)") (class "Default")
      (node (ref "M2D1") (pin "A") (pinfunction "A_A") (pintype "passive"))
      (node (ref "M2D2") (pin "C") (pinfunction "C_C") (pintype "passive"))
      (node (ref "M2R12") (pin "1") (pinfunction "1_1") (pintype "passive"))
    )
    (net (code "55") (name "Net-(M2Q1-G)") (class "Default")
      (node (ref "M2Q1") (pin "1") (pinfunction "G_1") (pintype "bidirectional"))
      (node (ref "M_FR") (pin "P11") (pinfunction "CP_P11") (pintype "output"))
    )
    (net (code "56") (name "Net-(M3C2-+)") (class "Default")
      (node (ref "M3C2") (pin "1") (pinfunction "+_1") (pintype "passive"))
      (node (ref "M3C3") (pin "1") (pinfunction "1_1") (pintype "passive"))
      (node (ref "M3Q1") (pin "4") (pinfunction "D_4") (pintype "bidirectional"))
      (node (ref "M_BL") (pin "P$19") (pinfunction "VCC_P$19") (pintype "power_in"))
      (node (ref "M_BL") (pin "P$20") (pinfunction "VCC_P$20") (pintype "power_in"))
      (node (ref "M_BL") (pin "P$21") (pinfunction "VCC_P$21") (pintype "power_in"))
      (node (ref "M_BL") (pin "P$22") (pinfunction "VCC_P$22") (pintype "power_in"))
      (node (ref "M_BL") (pin "P$23") (pinfunction "VCC_P$23") (pintype "power_in"))
      (node (ref "M_BL") (pin "P$24") (pinfunction "VCC_P$24") (pintype "power_in"))
      (node (ref "M_BL") (pin "P$25") (pinfunction "VCC_P$25") (pintype "power_in"))
      (node (ref "M_BL") (pin "P$26") (pinfunction "VCC_P$26") (pintype "power_in"))
      (node (ref "M_BL") (pin "P$27") (pinfunction "VCC_P$27") (pintype "power_in"))
      (node (ref "M_BL") (pin "P$28") (pinfunction "VCC_P$28") (pintype "power_in"))
      (node (ref "M_BL") (pin "P13") (pinfunction "VCC_P13") (pintype "power_in"))
      (node (ref "M_BL") (pin "P23") (pinfunction "VCC_P23") (pintype "power_in"))
      (node (ref "M_BL") (pin "P3") (pinfunction "VCC_P3") (pintype "power_in"))
      (node (ref "M_BL") (pin "SLUG1") (pinfunction "VCC_SLUG1") (pintype "power_in"))
    )
    (net (code "57") (name "Net-(M3D1-PadA)") (class "Default")
      (node (ref "M3D1") (pin "A") (pinfunction "A_A") (pintype "passive"))
      (node (ref "M3D2") (pin "C") (pinfunction "C_C") (pintype "passive"))
      (node (ref "M3R12") (pin "1") (pinfunction "1_1") (pintype "passive"))
    )
    (net (code "58") (name "Net-(M3Q1-G)") (class "Default")
      (node (ref "M3Q1") (pin "1") (pinfunction "G_1") (pintype "bidirectional"))
      (node (ref "M_BL") (pin "P11") (pinfunction "CP_P11") (pintype "output"))
    )
    (net (code "59") (name "Net-(M4C2-+)") (class "Default")
      (node (ref "M4C2") (pin "1") (pinfunction "+_1") (pintype "passive"))
      (node (ref "M4C3") (pin "1") (pinfunction "1_1") (pintype "passive"))
      (node (ref "M4Q1") (pin "4") (pinfunction "D_4") (pintype "bidirectional"))
      (node (ref "M_BR") (pin "P$19") (pinfunction "VCC_P$19") (pintype "power_in"))
      (node (ref "M_BR") (pin "P$20") (pinfunction "VCC_P$20") (pintype "power_in"))
      (node (ref "M_BR") (pin "P$21") (pinfunction "VCC_P$21") (pintype "power_in"))
      (node (ref "M_BR") (pin "P$22") (pinfunction "VCC_P$22") (pintype "power_in"))
      (node (ref "M_BR") (pin "P$23") (pinfunction "VCC_P$23") (pintype "power_in"))
      (node (ref "M_BR") (pin "P$24") (pinfunction "VCC_P$24") (pintype "power_in"))
      (node (ref "M_BR") (pin "P$25") (pinfunction "VCC_P$25") (pintype "power_in"))
      (node (ref "M_BR") (pin "P$26") (pinfunction "VCC_P$26") (pintype "power_in"))
      (node (ref "M_BR") (pin "P$27") (pinfunction "VCC_P$27") (pintype "power_in"))
      (node (ref "M_BR") (pin "P$28") (pinfunction "VCC_P$28") (pintype "power_in"))
      (node (ref "M_BR") (pin "P13") (pinfunction "VCC_P13") (pintype "power_in"))
      (node (ref "M_BR") (pin "P23") (pinfunction "VCC_P23") (pintype "power_in"))
      (node (ref "M_BR") (pin "P3") (pinfunction "VCC_P3") (pintype "power_in"))
      (node (ref "M_BR") (pin "SLUG1") (pinfunction "VCC_SLUG1") (pintype "power_in"))
    )
    (net (code "60") (name "Net-(M4D1-PadA)") (class "Default")
      (node (ref "M4D1") (pin "A") (pinfunction "A_A") (pintype "passive"))
      (node (ref "M4D2") (pin "C") (pinfunction "C_C") (pintype "passive"))
      (node (ref "M4R12") (pin "1") (pinfunction "1_1") (pintype "passive"))
    )
    (net (code "61") (name "Net-(M4Q1-G)") (class "Default")
      (node (ref "M4Q1") (pin "1") (pinfunction "G_1") (pintype "bidirectional"))
      (node (ref "M_BR") (pin "P11") (pinfunction "CP_P11") (pintype "output"))
    )
    (net (code "62") (name "Net-(MUX_L1-CHAN0)") (class "Default")
      (node (ref "MUX_L1") (pin "9") (pinfunction "CHAN0_9") (pintype "bidirectional"))
      (node (ref "Q16") (pin "E") (pinfunction "E1_E") (pintype "passive"))
    )
    (net (code "63") (name "Net-(MUX_L1-CHAN1)") (class "Default")
      (node (ref "MUX_L1") (pin "8") (pinfunction "CHAN1_8") (pintype "bidirectional"))
      (node (ref "Q15") (pin "E") (pinfunction "E1_E") (pintype "passive"))
    )
    (net (code "64") (name "Net-(MUX_L1-CHAN2)") (class "Default")
      (node (ref "MUX_L1") (pin "7") (pinfunction "CHAN2_7") (pintype "bidirectional"))
      (node (ref "Q14") (pin "E") (pinfunction "E1_E") (pintype "passive"))
    )
    (net (code "65") (name "Net-(MUX_L1-CHAN3)") (class "Default")
      (node (ref "MUX_L1") (pin "6") (pinfunction "CHAN3_6") (pintype "bidirectional"))
      (node (ref "Q13") (pin "E") (pinfunction "E1_E") (pintype "passive"))
    )
    (net (code "66") (name "Net-(MUX_L1-CHAN4)") (class "Default")
      (node (ref "MUX_L1") (pin "5") (pinfunction "CHAN4_5") (pintype "bidirectional"))
      (node (ref "Q12") (pin "E") (pinfunction "E1_E") (pintype "passive"))
    )
    (net (code "67") (name "Net-(MUX_L1-CHAN5)") (class "Default")
      (node (ref "MUX_L1") (pin "4") (pinfunction "CHAN5_4") (pintype "bidirectional"))
      (node (ref "Q11") (pin "E") (pinfunction "E1_E") (pintype "passive"))
    )
    (net (code "68") (name "Net-(MUX_L1-CHAN6)") (class "Default")
      (node (ref "MUX_L1") (pin "3") (pinfunction "CHAN6_3") (pintype "bidirectional"))
      (node (ref "Q10") (pin "E") (pinfunction "E1_E") (pintype "passive"))
    )
    (net (code "69") (name "Net-(MUX_L1-CHAN7)") (class "Default")
      (node (ref "MUX_L1") (pin "2") (pinfunction "CHAN7_2") (pintype "bidirectional"))
      (node (ref "Q9") (pin "E") (pinfunction "E1_E") (pintype "passive"))
    )
    (net (code "70") (name "Net-(MUX_L1-CHAN8)") (class "Default")
      (node (ref "MUX_L1") (pin "23") (pinfunction "CHAN8_23") (pintype "bidirectional"))
      (node (ref "Q8") (pin "E") (pinfunction "E1_E") (pintype "passive"))
    )
    (net (code "71") (name "Net-(MUX_L1-CHAN9)") (class "Default")
      (node (ref "MUX_L1") (pin "22") (pinfunction "CHAN9_22") (pintype "bidirectional"))
      (node (ref "Q7") (pin "E") (pinfunction "E1_E") (pintype "passive"))
    )
    (net (code "72") (name "Net-(MUX_L1-CHAN10)") (class "Default")
      (node (ref "MUX_L1") (pin "21") (pinfunction "CHAN10_21") (pintype "bidirectional"))
      (node (ref "Q6") (pin "E") (pinfunction "E1_E") (pintype "passive"))
    )
    (net (code "73") (name "Net-(MUX_L1-CHAN11)") (class "Default")
      (node (ref "MUX_L1") (pin "20") (pinfunction "CHAN11_20") (pintype "bidirectional"))
      (node (ref "Q5") (pin "E") (pinfunction "E1_E") (pintype "passive"))
    )
    (net (code "74") (name "Net-(MUX_L1-CHAN12)") (class "Default")
      (node (ref "MUX_L1") (pin "19") (pinfunction "CHAN12_19") (pintype "bidirectional"))
      (node (ref "Q4") (pin "E") (pinfunction "E1_E") (pintype "passive"))
    )
    (net (code "75") (name "Net-(MUX_L1-CHAN13)") (class "Default")
      (node (ref "MUX_L1") (pin "18") (pinfunction "CHAN13_18") (pintype "bidirectional"))
      (node (ref "Q3") (pin "E") (pinfunction "E1_E") (pintype "passive"))
    )
    (net (code "76") (name "Net-(MUX_L1-CHAN14)") (class "Default")
      (node (ref "MUX_L1") (pin "17") (pinfunction "CHAN14_17") (pintype "bidirectional"))
      (node (ref "Q2") (pin "E") (pinfunction "E1_E") (pintype "passive"))
    )
    (net (code "77") (name "Net-(MUX_L1-CHAN15)") (class "Default")
      (node (ref "MUX_L1") (pin "16") (pinfunction "CHAN15_16") (pintype "bidirectional"))
      (node (ref "Q1") (pin "E") (pinfunction "E1_E") (pintype "passive"))
    )
    (net (code "78") (name "Net-(MUX_L1-EN)") (class "Default")
      (node (ref "2R1") (pin "2") (pinfunction "2_2") (pintype "passive"))
      (node (ref "MUX_L1") (pin "15") (pinfunction "EN_15") (pintype "input"))
    )
    (net (code "79") (name "Net-(MUX_L2-CHAN0)") (class "Default")
      (node (ref "MUX_L2") (pin "9") (pinfunction "CHAN0_9") (pintype "bidirectional"))
      (node (ref "Q32") (pin "E") (pinfunction "E1_E") (pintype "passive"))
    )
    (net (code "80") (name "Net-(MUX_L2-CHAN1)") (class "Default")
      (node (ref "MUX_L2") (pin "8") (pinfunction "CHAN1_8") (pintype "bidirectional"))
      (node (ref "Q31") (pin "E") (pinfunction "E1_E") (pintype "passive"))
    )
    (net (code "81") (name "Net-(MUX_L2-CHAN2)") (class "Default")
      (node (ref "MUX_L2") (pin "7") (pinfunction "CHAN2_7") (pintype "bidirectional"))
      (node (ref "Q30") (pin "E") (pinfunction "E1_E") (pintype "passive"))
    )
    (net (code "82") (name "Net-(MUX_L2-CHAN3)") (class "Default")
      (node (ref "MUX_L2") (pin "6") (pinfunction "CHAN3_6") (pintype "bidirectional"))
      (node (ref "Q29") (pin "E") (pinfunction "E1_E") (pintype "passive"))
    )
    (net (code "83") (name "Net-(MUX_L2-CHAN4)") (class "Default")
      (node (ref "MUX_L2") (pin "5") (pinfunction "CHAN4_5") (pintype "bidirectional"))
      (node (ref "Q28") (pin "E") (pinfunction "E1_E") (pintype "passive"))
    )
    (net (code "84") (name "Net-(MUX_L2-CHAN5)") (class "Default")
      (node (ref "MUX_L2") (pin "4") (pinfunction "CHAN5_4") (pintype "bidirectional"))
      (node (ref "Q27") (pin "E") (pinfunction "E1_E") (pintype "passive"))
    )
    (net (code "85") (name "Net-(MUX_L2-CHAN6)") (class "Default")
      (node (ref "MUX_L2") (pin "3") (pinfunction "CHAN6_3") (pintype "bidirectional"))
      (node (ref "Q26") (pin "E") (pinfunction "E1_E") (pintype "passive"))
    )
    (net (code "86") (name "Net-(MUX_L2-CHAN7)") (class "Default")
      (node (ref "MUX_L2") (pin "2") (pinfunction "CHAN7_2") (pintype "bidirectional"))
      (node (ref "Q25") (pin "E") (pinfunction "E1_E") (pintype "passive"))
    )
    (net (code "87") (name "Net-(MUX_L2-CHAN8)") (class "Default")
      (node (ref "MUX_L2") (pin "23") (pinfunction "CHAN8_23") (pintype "bidirectional"))
      (node (ref "Q24") (pin "E") (pinfunction "E1_E") (pintype "passive"))
    )
    (net (code "88") (name "Net-(MUX_L2-CHAN9)") (class "Default")
      (node (ref "MUX_L2") (pin "22") (pinfunction "CHAN9_22") (pintype "bidirectional"))
      (node (ref "Q23") (pin "E") (pinfunction "E1_E") (pintype "passive"))
    )
    (net (code "89") (name "Net-(MUX_L2-CHAN10)") (class "Default")
      (node (ref "MUX_L2") (pin "21") (pinfunction "CHAN10_21") (pintype "bidirectional"))
      (node (ref "Q22") (pin "E") (pinfunction "E1_E") (pintype "passive"))
    )
    (net (code "90") (name "Net-(MUX_L2-CHAN11)") (class "Default")
      (node (ref "MUX_L2") (pin "20") (pinfunction "CHAN11_20") (pintype "bidirectional"))
      (node (ref "Q21") (pin "E") (pinfunction "E1_E") (pintype "passive"))
    )
    (net (code "91") (name "Net-(MUX_L2-CHAN12)") (class "Default")
      (node (ref "MUX_L2") (pin "19") (pinfunction "CHAN12_19") (pintype "bidirectional"))
      (node (ref "Q20") (pin "E") (pinfunction "E1_E") (pintype "passive"))
    )
    (net (code "92") (name "Net-(MUX_L2-CHAN13)") (class "Default")
      (node (ref "MUX_L2") (pin "18") (pinfunction "CHAN13_18") (pintype "bidirectional"))
      (node (ref "Q19") (pin "E") (pinfunction "E1_E") (pintype "passive"))
    )
    (net (code "93") (name "Net-(MUX_L2-CHAN14)") (class "Default")
      (node (ref "MUX_L2") (pin "17") (pinfunction "CHAN14_17") (pintype "bidirectional"))
      (node (ref "Q18") (pin "E") (pinfunction "E1_E") (pintype "passive"))
    )
    (net (code "94") (name "Net-(MUX_L2-CHAN15)") (class "Default")
      (node (ref "MUX_L2") (pin "16") (pinfunction "CHAN15_16") (pintype "bidirectional"))
      (node (ref "Q17") (pin "E") (pinfunction "E1_E") (pintype "passive"))
    )
    (net (code "95") (name "Net-(MUX_L2-EN)") (class "Default")
      (node (ref "2R2") (pin "2") (pinfunction "2_2") (pintype "passive"))
      (node (ref "MUX_L2") (pin "15") (pinfunction "EN_15") (pintype "input"))
    )
    (net (code "96") (name "Net-(MUX_L3-CHAN12)") (class "Default")
      (node (ref "MUX_L3") (pin "19") (pinfunction "CHAN12_19") (pintype "bidirectional"))
      (node (ref "Q36") (pin "E") (pinfunction "E1_E") (pintype "passive"))
    )
    (net (code "97") (name "Net-(MUX_L3-CHAN13)") (class "Default")
      (node (ref "MUX_L3") (pin "18") (pinfunction "CHAN13_18") (pintype "bidirectional"))
      (node (ref "Q35") (pin "E") (pinfunction "E1_E") (pintype "passive"))
    )
    (net (code "98") (name "Net-(MUX_L3-CHAN14)") (class "Default")
      (node (ref "MUX_L3") (pin "17") (pinfunction "CHAN14_17") (pintype "bidirectional"))
      (node (ref "Q34") (pin "E") (pinfunction "E1_E") (pintype "passive"))
    )
    (net (code "99") (name "Net-(MUX_L3-CHAN15)") (class "Default")
      (node (ref "MUX_L3") (pin "16") (pinfunction "CHAN15_16") (pintype "bidirectional"))
      (node (ref "Q33") (pin "E") (pinfunction "E1_E") (pintype "passive"))
    )
    (net (code "100") (name "Net-(MUX_L3-EN)") (class "Default")
      (node (ref "2R3") (pin "2") (pinfunction "2_2") (pintype "passive"))
      (node (ref "MUX_L3") (pin "15") (pinfunction "EN_15") (pintype "input"))
    )
    (net (code "101") (name "Net-(M_BL-CS)") (class "Default")
      (node (ref "M3R10") (pin "2") (pinfunction "2_2") (pintype "passive"))
      (node (ref "M3R8") (pin "2") (pinfunction "2_2") (pintype "passive"))
      (node (ref "M_BL") (pin "P8") (pinfunction "CS_P8") (pintype "output"))
    )
    (net (code "102") (name "Net-(M_BL-CS_DIS)") (class "Default")
      (node (ref "M3R9") (pin "2") (pinfunction "2_2") (pintype "passive"))
      (node (ref "M_BL") (pin "P6") (pinfunction "CS_DIS_P6") (pintype "input"))
    )
    (net (code "103") (name "Net-(M_BL-EN_A)") (class "Default")
      (node (ref "M3R1") (pin "2") (pinfunction "2_2") (pintype "passive"))
      (node (ref "M3R4") (pin "1") (pinfunction "1_1") (pintype "passive"))
      (node (ref "M_BL") (pin "P5") (pinfunction "EN_A_P5") (pintype "bidirectional"))
    )
    (net (code "104") (name "Net-(M_BL-EN_B)") (class "Default")
      (node (ref "M3R2") (pin "2") (pinfunction "2_2") (pintype "passive"))
      (node (ref "M3R3") (pin "1") (pinfunction "1_1") (pintype "passive"))
      (node (ref "M_BL") (pin "P9") (pinfunction "EN_B_P9") (pintype "bidirectional"))
    )
    (net (code "105") (name "Net-(M_BL-IN_A)") (class "Default")
      (node (ref "M3R5") (pin "2") (pinfunction "2_2") (pintype "passive"))
      (node (ref "M_BL") (pin "P4") (pinfunction "IN_A_P4") (pintype "input"))
    )
    (net (code "106") (name "Net-(M_BL-IN_B)") (class "Default")
      (node (ref "M3R6") (pin "2") (pinfunction "2_2") (pintype "passive"))
      (node (ref "M_BL") (pin "P10") (pinfunction "IN_B_P10") (pintype "input"))
    )
    (net (code "107") (name "Net-(M_BL-PWM_IN)") (class "Default")
      (node (ref "M3R7") (pin "2") (pinfunction "2_2") (pintype "passive"))
      (node (ref "M_BL") (pin "P7") (pinfunction "PWM_IN_P7") (pintype "input"))
    )
    (net (code "108") (name "Net-(M_BR-CS)") (class "Default")
      (node (ref "M4R10") (pin "2") (pinfunction "2_2") (pintype "passive"))
      (node (ref "M4R8") (pin "2") (pinfunction "2_2") (pintype "passive"))
      (node (ref "M_BR") (pin "P8") (pinfunction "CS_P8") (pintype "output"))
    )
    (net (code "109") (name "Net-(M_BR-CS_DIS)") (class "Default")
      (node (ref "M4R9") (pin "2") (pinfunction "2_2") (pintype "passive"))
      (node (ref "M_BR") (pin "P6") (pinfunction "CS_DIS_P6") (pintype "input"))
    )
    (net (code "110") (name "Net-(M_BR-EN_A)") (class "Default")
      (node (ref "M4R1") (pin "2") (pinfunction "2_2") (pintype "passive"))
      (node (ref "M4R4") (pin "1") (pinfunction "1_1") (pintype "passive"))
      (node (ref "M_BR") (pin "P5") (pinfunction "EN_A_P5") (pintype "bidirectional"))
    )
    (net (code "111") (name "Net-(M_BR-EN_B)") (class "Default")
      (node (ref "M4R2") (pin "2") (pinfunction "2_2") (pintype "passive"))
      (node (ref "M4R3") (pin "1") (pinfunction "1_1") (pintype "passive"))
      (node (ref "M_BR") (pin "P9") (pinfunction "EN_B_P9") (pintype "bidirectional"))
    )
    (net (code "112") (name "Net-(M_BR-IN_A)") (class "Default")
      (node (ref "M4R5") (pin "2") (pinfunction "2_2") (pintype "passive"))
      (node (ref "M_BR") (pin "P4") (pinfunction "IN_A_P4") (pintype "input"))
    )
    (net (code "113") (name "Net-(M_BR-IN_B)") (class "Default")
      (node (ref "M4R6") (pin "2") (pinfunction "2_2") (pintype "passive"))
      (node (ref "M_BR") (pin "P10") (pinfunction "IN_B_P10") (pintype "input"))
    )
    (net (code "114") (name "Net-(M_BR-PWM_IN)") (class "Default")
      (node (ref "M4R7") (pin "2") (pinfunction "2_2") (pintype "passive"))
      (node (ref "M_BR") (pin "P7") (pinfunction "PWM_IN_P7") (pintype "input"))
    )
    (net (code "115") (name "Net-(M_FL-CS)") (class "Default")
      (node (ref "M1R10") (pin "2") (pinfunction "2_2") (pintype "passive"))
      (node (ref "M1R8") (pin "2") (pinfunction "2_2") (pintype "passive"))
      (node (ref "M_FL") (pin "P8") (pinfunction "CS_P8") (pintype "output"))
    )
    (net (code "116") (name "Net-(M_FL-CS_DIS)") (class "Default")
      (node (ref "M1R9") (pin "2") (pinfunction "2_2") (pintype "passive"))
      (node (ref "M_FL") (pin "P6") (pinfunction "CS_DIS_P6") (pintype "input"))
    )
    (net (code "117") (name "Net-(M_FL-EN_A)") (class "Default")
      (node (ref "M1R1") (pin "2") (pinfunction "2_2") (pintype "passive"))
      (node (ref "M1R4") (pin "1") (pinfunction "1_1") (pintype "passive"))
      (node (ref "M_FL") (pin "P5") (pinfunction "EN_A_P5") (pintype "bidirectional"))
    )
    (net (code "118") (name "Net-(M_FL-EN_B)") (class "Default")
      (node (ref "M1R2") (pin "2") (pinfunction "2_2") (pintype "passive"))
      (node (ref "M1R3") (pin "1") (pinfunction "1_1") (pintype "passive"))
      (node (ref "M_FL") (pin "P9") (pinfunction "EN_B_P9") (pintype "bidirectional"))
    )
    (net (code "119") (name "Net-(M_FL-IN_A)") (class "Default")
      (node (ref "M1R5") (pin "2") (pinfunction "2_2") (pintype "passive"))
      (node (ref "M_FL") (pin "P4") (pinfunction "IN_A_P4") (pintype "input"))
    )
    (net (code "120") (name "Net-(M_FL-IN_B)") (class "Default")
      (node (ref "M1R6") (pin "2") (pinfunction "2_2") (pintype "passive"))
      (node (ref "M_FL") (pin "P10") (pinfunction "IN_B_P10") (pintype "input"))
    )
    (net (code "121") (name "Net-(M_FL-PWM_IN)") (class "Default")
      (node (ref "M1R7") (pin "2") (pinfunction "2_2") (pintype "passive"))
      (node (ref "M_FL") (pin "P7") (pinfunction "PWM_IN_P7") (pintype "input"))
    )
    (net (code "122") (name "Net-(M_FR-CS)") (class "Default")
      (node (ref "M2R10") (pin "2") (pinfunction "2_2") (pintype "passive"))
      (node (ref "M2R8") (pin "2") (pinfunction "2_2") (pintype "passive"))
      (node (ref "M_FR") (pin "P8") (pinfunction "CS_P8") (pintype "output"))
    )
    (net (code "123") (name "Net-(M_FR-CS_DIS)") (class "Default")
      (node (ref "M2R9") (pin "2") (pinfunction "2_2") (pintype "passive"))
      (node (ref "M_FR") (pin "P6") (pinfunction "CS_DIS_P6") (pintype "input"))
    )
    (net (code "124") (name "Net-(M_FR-EN_A)") (class "Default")
      (node (ref "M2R1") (pin "2") (pinfunction "2_2") (pintype "passive"))
      (node (ref "M2R4") (pin "1") (pinfunction "1_1") (pintype "passive"))
      (node (ref "M_FR") (pin "P5") (pinfunction "EN_A_P5") (pintype "bidirectional"))
    )
    (net (code "125") (name "Net-(M_FR-EN_B)") (class "Default")
      (node (ref "M2R2") (pin "2") (pinfunction "2_2") (pintype "passive"))
      (node (ref "M2R3") (pin "1") (pinfunction "1_1") (pintype "passive"))
      (node (ref "M_FR") (pin "P9") (pinfunction "EN_B_P9") (pintype "bidirectional"))
    )
    (net (code "126") (name "Net-(M_FR-IN_A)") (class "Default")
      (node (ref "M2R5") (pin "2") (pinfunction "2_2") (pintype "passive"))
      (node (ref "M_FR") (pin "P4") (pinfunction "IN_A_P4") (pintype "input"))
    )
    (net (code "127") (name "Net-(M_FR-IN_B)") (class "Default")
      (node (ref "M2R6") (pin "2") (pinfunction "2_2") (pintype "passive"))
      (node (ref "M_FR") (pin "P10") (pinfunction "IN_B_P10") (pintype "input"))
    )
    (net (code "128") (name "Net-(M_FR-PWM_IN)") (class "Default")
      (node (ref "M2R7") (pin "2") (pinfunction "2_2") (pintype "passive"))
      (node (ref "M_FR") (pin "P7") (pinfunction "PWM_IN_P7") (pintype "input"))
    )
    (net (code "129") (name "Net-(RST-1)") (class "Default")
      (node (ref "R2") (pin "2") (pinfunction "2_2") (pintype "passive"))
      (node (ref "RST") (pin "P$1") (pinfunction "1_P$1") (pintype "passive"))
    )
    (net (code "130") (name "Net-(U$2-PB1{slash}ADC12_IN9{slash}TIM3_CH4)") (class "Default")
      (node (ref "R5") (pin "2") (pinfunction "2_2") (pintype "passive"))
      (node (ref "U$2") (pin "19") (pinfunction "PB1/ADC12_IN9/TIM3_CH4_19") (pintype "bidirectional"))
    )
    (net (code "131") (name "Net-(U1-BOOT)") (class "Default")
      (node (ref "1C3") (pin "1") (pinfunction "1_1") (pintype "passive"))
      (node (ref "U1") (pin "1") (pinfunction "BOOT_1") (pintype "output"))
    )
    (net (code "132") (name "Net-(U1-VSNS)") (class "Default")
      (node (ref "1R1") (pin "1") (pinfunction "1_1") (pintype "passive"))
      (node (ref "1R2") (pin "2") (pinfunction "2_2") (pintype "passive"))
      (node (ref "U1") (pin "4") (pinfunction "VSNS_4") (pintype "input"))
    )
    (net (code "133") (name "OSC_IN") (class "Default")
      (node (ref "C6") (pin "2") (pinfunction "2_2") (pintype "passive"))
      (node (ref "U$2") (pin "5") (pinfunction "PD0-OSC_IN_5") (pintype "input"))
      (node (ref "Y1") (pin "P$2") (pinfunction "2_P$2") (pintype "passive"))
    )
    (net (code "134") (name "OSC_OUT") (class "Default")
      (node (ref "C7") (pin "2") (pinfunction "2_2") (pintype "passive"))
      (node (ref "U$2") (pin "6") (pinfunction "PD1-OSC_OUT_6") (pintype "input"))
      (node (ref "Y1") (pin "P$1") (pinfunction "1_P$1") (pintype "passive"))
    )
    (net (code "135") (name "RESET") (class "Default")
      (node (ref "R1") (pin "1") (pinfunction "1_1") (pintype "passive"))
      (node (ref "RST") (pin "P$2") (pinfunction "2_P$2") (pintype "passive"))
      (node (ref "U$2") (pin "7") (pinfunction "NRST_7") (pintype "input"))
    )
    (net (code "136") (name "RX1") (class "Default")
      (node (ref "U$2") (pin "31") (pinfunction "PA10/USART1_RX/TIM1_CH3_31") (pintype "bidirectional"))
      (node (ref "X2") (pin "6") (pinfunction "6_6") (pintype "passive"))
    )
    (net (code "137") (name "RX3") (class "Default")
      (node (ref "U$15") (pin "11") (pinfunction "11_11") (pintype "passive"))
      (node (ref "U$2") (pin "22") (pinfunction "PB11/I2C2_SDA/USART3_RX_22") (pintype "input"))
    )
    (net (code "138") (name "SCK") (class "Default")
      (node (ref "MOUSE") (pin "6") (pinfunction "6_6") (pintype "passive"))
      (node (ref "U$2") (pin "39") (pinfunction "PB3/JTDO_39") (pintype "bidirectional"))
    )
    (net (code "139") (name "SS") (class "Default")
      (node (ref "MOUSE") (pin "5") (pinfunction "5_5") (pintype "passive"))
      (node (ref "U$2") (pin "38") (pinfunction "PA15/JTDI_38") (pintype "bidirectional"))
    )
    (net (code "140") (name "SWCLK") (class "Default")
      (node (ref "U$2") (pin "37") (pinfunction "PA14/JTCK/SWCLK_37") (pintype "bidirectional"))
      (node (ref "X2") (pin "2") (pinfunction "2_2") (pintype "passive"))
    )
    (net (code "141") (name "SWDIO") (class "Default")
      (node (ref "U$2") (pin "34") (pinfunction "PA13/JTMS/SWDIO_34") (pintype "bidirectional"))
      (node (ref "X2") (pin "3") (pinfunction "3_3") (pintype "passive"))
    )
    (net (code "142") (name "TX1") (class "Default")
      (node (ref "U$2") (pin "30") (pinfunction "PA9/USART1_TX/TIM1_CH2_30") (pintype "input"))
      (node (ref "X2") (pin "5") (pinfunction "5_5") (pintype "passive"))
    )
    (net (code "143") (name "TX3") (class "Default")
      (node (ref "U$15") (pin "9") (pinfunction "9_9") (pintype "passive"))
      (node (ref "U$2") (pin "21") (pinfunction "PB10/I2C2_SCL/USART3_TX_21") (pintype "input"))
    )
    (net (code "144") (name "VCCA") (class "Default")
      (node (ref "C4") (pin "2") (pinfunction "2_2") (pintype "passive"))
      (node (ref "C5") (pin "2") (pinfunction "2_2") (pintype "passive"))
      (node (ref "FB1") (pin "2") (pinfunction "2_2") (pintype "passive"))
      (node (ref "LDR") (pin "1") (pinfunction "1_1") (pintype "passive"))
      (node (ref "Q1") (pin "C") (pinfunction "C1_C") (pintype "passive"))
      (node (ref "Q10") (pin "C") (pinfunction "C1_C") (pintype "passive"))
      (node (ref "Q11") (pin "C") (pinfunction "C1_C") (pintype "passive"))
      (node (ref "Q12") (pin "C") (pinfunction "C1_C") (pintype "passive"))
      (node (ref "Q13") (pin "C") (pinfunction "C1_C") (pintype "passive"))
      (node (ref "Q14") (pin "C") (pinfunction "C1_C") (pintype "passive"))
      (node (ref "Q15") (pin "C") (pinfunction "C1_C") (pintype "passive"))
      (node (ref "Q16") (pin "C") (pinfunction "C1_C") (pintype "passive"))
      (node (ref "Q17") (pin "C") (pinfunction "C1_C") (pintype "passive"))
      (node (ref "Q18") (pin "C") (pinfunction "C1_C") (pintype "passive"))
      (node (ref "Q19") (pin "C") (pinfunction "C1_C") (pintype "passive"))
      (node (ref "Q2") (pin "C") (pinfunction "C1_C") (pintype "passive"))
      (node (ref "Q20") (pin "C") (pinfunction "C1_C") (pintype "passive"))
      (node (ref "Q21") (pin "C") (pinfunction "C1_C") (pintype "passive"))
      (node (ref "Q22") (pin "C") (pinfunction "C1_C") (pintype "passive"))
      (node (ref "Q23") (pin "C") (pinfunction "C1_C") (pintype "passive"))
      (node (ref "Q24") (pin "C") (pinfunction "C1_C") (pintype "passive"))
      (node (ref "Q25") (pin "C") (pinfunction "C1_C") (pintype "passive"))
      (node (ref "Q26") (pin "C") (pinfunction "C1_C") (pintype "passive"))
      (node (ref "Q27") (pin "C") (pinfunction "C1_C") (pintype "passive"))
      (node (ref "Q28") (pin "C") (pinfunction "C1_C") (pintype "passive"))
      (node (ref "Q29") (pin "C") (pinfunction "C1_C") (pintype "passive"))
      (node (ref "Q3") (pin "C") (pinfunction "C1_C") (pintype "passive"))
      (node (ref "Q30") (pin "C") (pinfunction "C1_C") (pintype "passive"))
      (node (ref "Q31") (pin "C") (pinfunction "C1_C") (pintype "passive"))
      (node (ref "Q32") (pin "C") (pinfunction "C1_C") (pintype "passive"))
      (node (ref "Q33") (pin "C") (pinfunction "C1_C") (pintype "passive"))
      (node (ref "Q34") (pin "C") (pinfunction "C1_C") (pintype "passive"))
      (node (ref "Q35") (pin "C") (pinfunction "C1_C") (pintype "passive"))
      (node (ref "Q36") (pin "C") (pinfunction "C1_C") (pintype "passive"))
      (node (ref "Q4") (pin "C") (pinfunction "C1_C") (pintype "passive"))
      (node (ref "Q5") (pin "C") (pinfunction "C1_C") (pintype "passive"))
      (node (ref "Q6") (pin "C") (pinfunction "C1_C") (pintype "passive"))
      (node (ref "Q7") (pin "C") (pinfunction "C1_C") (pintype "passive"))
      (node (ref "Q8") (pin "C") (pinfunction "C1_C") (pintype "passive"))
      (node (ref "Q9") (pin "C") (pinfunction "C1_C") (pintype "passive"))
      (node (ref "U$2") (pin "9") (pinfunction "VDD_A_9") (pintype "power_in"))
    )
    (net (code "145") (name "V_BATT") (class "Default")
      (node (ref "1C1") (pin "1") (pinfunction "1_1") (pintype "passive"))
      (node (ref "1C2") (pin "1") (pinfunction "1_1") (pintype "passive"))
      (node (ref "M1Q1") (pin "3") (pinfunction "S_3") (pintype "bidirectional"))
      (node (ref "M2Q1") (pin "3") (pinfunction "S_3") (pintype "bidirectional"))
      (node (ref "M3Q1") (pin "3") (pinfunction "S_3") (pintype "bidirectional"))
      (node (ref "M4Q1") (pin "3") (pinfunction "S_3") (pintype "bidirectional"))
      (node (ref "M_BL") (pin "P12") (pinfunction "VBAT_P12") (pintype "power_in"))
      (node (ref "M_BR") (pin "P12") (pinfunction "VBAT_P12") (pintype "power_in"))
      (node (ref "M_FL") (pin "P12") (pinfunction "VBAT_P12") (pintype "power_in"))
      (node (ref "M_FR") (pin "P12") (pinfunction "VBAT_P12") (pintype "power_in"))
      (node (ref "R6") (pin "2") (pinfunction "2_2") (pintype "passive"))
      (node (ref "U$1") (pin "+") (pinfunction "P$V+_+") (pintype "bidirectional"))
      (node (ref "U1") (pin "7") (pinfunction "VIN_7") (pintype "power_in"))
    )
    (net (code "146") (name "unconnected-(LS1-S-Pad3)") (class "Default")
      (node (ref "LS1") (pin "3") (pinfunction "S_3") (pintype "passive"))
    )
    (net (code "147") (name "unconnected-(MUX_L3-CHAN0-Pad9)") (class "Default")
      (node (ref "MUX_L3") (pin "9") (pinfunction "CHAN0_9") (pintype "bidirectional"))
    )
    (net (code "148") (name "unconnected-(MUX_L3-CHAN1-Pad8)") (class "Default")
      (node (ref "MUX_L3") (pin "8") (pinfunction "CHAN1_8") (pintype "bidirectional"))
    )
    (net (code "149") (name "unconnected-(MUX_L3-CHAN2-Pad7)") (class "Default")
      (node (ref "MUX_L3") (pin "7") (pinfunction "CHAN2_7") (pintype "bidirectional"))
    )
    (net (code "150") (name "unconnected-(MUX_L3-CHAN3-Pad6)") (class "Default")
      (node (ref "MUX_L3") (pin "6") (pinfunction "CHAN3_6") (pintype "bidirectional"))
    )
    (net (code "151") (name "unconnected-(MUX_L3-CHAN4-Pad5)") (class "Default")
      (node (ref "MUX_L3") (pin "5") (pinfunction "CHAN4_5") (pintype "bidirectional"))
    )
    (net (code "152") (name "unconnected-(MUX_L3-CHAN5-Pad4)") (class "Default")
      (node (ref "MUX_L3") (pin "4") (pinfunction "CHAN5_4") (pintype "bidirectional"))
    )
    (net (code "153") (name "unconnected-(MUX_L3-CHAN6-Pad3)") (class "Default")
      (node (ref "MUX_L3") (pin "3") (pinfunction "CHAN6_3") (pintype "bidirectional"))
    )
    (net (code "154") (name "unconnected-(MUX_L3-CHAN7-Pad2)") (class "Default")
      (node (ref "MUX_L3") (pin "2") (pinfunction "CHAN7_2") (pintype "bidirectional"))
    )
    (net (code "155") (name "unconnected-(MUX_L3-CHAN8-Pad23)") (class "Default")
      (node (ref "MUX_L3") (pin "23") (pinfunction "CHAN8_23") (pintype "bidirectional"))
    )
    (net (code "156") (name "unconnected-(MUX_L3-CHAN9-Pad22)") (class "Default")
      (node (ref "MUX_L3") (pin "22") (pinfunction "CHAN9_22") (pintype "bidirectional"))
    )
    (net (code "157") (name "unconnected-(MUX_L3-CHAN10-Pad21)") (class "Default")
      (node (ref "MUX_L3") (pin "21") (pinfunction "CHAN10_21") (pintype "bidirectional"))
    )
    (net (code "158") (name "unconnected-(MUX_L3-CHAN11-Pad20)") (class "Default")
      (node (ref "MUX_L3") (pin "20") (pinfunction "CHAN11_20") (pintype "bidirectional"))
    )
    (net (code "159") (name "unconnected-(M_BL-NC-PadP2)") (class "Default")
      (node (ref "M_BL") (pin "P2") (pinfunction "NC_P2") (pintype "no_connect"))
    )
    (net (code "160") (name "unconnected-(M_BL-NC-PadP14)") (class "Default")
      (node (ref "M_BL") (pin "P14") (pinfunction "NC_P14") (pintype "no_connect"))
    )
    (net (code "161") (name "unconnected-(M_BL-NC-PadP17)") (class "Default")
      (node (ref "M_BL") (pin "P17") (pinfunction "NC_P17") (pintype "no_connect"))
    )
    (net (code "162") (name "unconnected-(M_BL-NC-PadP22)") (class "Default")
      (node (ref "M_BL") (pin "P22") (pinfunction "NC_P22") (pintype "no_connect"))
    )
    (net (code "163") (name "unconnected-(M_BL-NC-PadP24)") (class "Default")
      (node (ref "M_BL") (pin "P24") (pinfunction "NC_P24") (pintype "no_connect"))
    )
    (net (code "164") (name "unconnected-(M_BL-NC-PadP29)") (class "Default")
      (node (ref "M_BL") (pin "P29") (pinfunction "NC_P29") (pintype "no_connect"))
    )
    (net (code "165") (name "unconnected-(M_BR-NC-PadP2)") (class "Default")
      (node (ref "M_BR") (pin "P2") (pinfunction "NC_P2") (pintype "no_connect"))
    )
    (net (code "166") (name "unconnected-(M_BR-NC-PadP14)") (class "Default")
      (node (ref "M_BR") (pin "P14") (pinfunction "NC_P14") (pintype "no_connect"))
    )
    (net (code "167") (name "unconnected-(M_BR-NC-PadP17)") (class "Default")
      (node (ref "M_BR") (pin "P17") (pinfunction "NC_P17") (pintype "no_connect"))
    )
    (net (code "168") (name "unconnected-(M_BR-NC-PadP22)") (class "Default")
      (node (ref "M_BR") (pin "P22") (pinfunction "NC_P22") (pintype "no_connect"))
    )
    (net (code "169") (name "unconnected-(M_BR-NC-PadP24)") (class "Default")
      (node (ref "M_BR") (pin "P24") (pinfunction "NC_P24") (pintype "no_connect"))
    )
    (net (code "170") (name "unconnected-(M_BR-NC-PadP29)") (class "Default")
      (node (ref "M_BR") (pin "P29") (pinfunction "NC_P29") (pintype "no_connect"))
    )
    (net (code "171") (name "unconnected-(M_FL-NC-PadP2)") (class "Default")
      (node (ref "M_FL") (pin "P2") (pinfunction "NC_P2") (pintype "no_connect"))
    )
    (net (code "172") (name "unconnected-(M_FL-NC-PadP14)") (class "Default")
      (node (ref "M_FL") (pin "P14") (pinfunction "NC_P14") (pintype "no_connect"))
    )
    (net (code "173") (name "unconnected-(M_FL-NC-PadP17)") (class "Default")
      (node (ref "M_FL") (pin "P17") (pinfunction "NC_P17") (pintype "no_connect"))
    )
    (net (code "174") (name "unconnected-(M_FL-NC-PadP22)") (class "Default")
      (node (ref "M_FL") (pin "P22") (pinfunction "NC_P22") (pintype "no_connect"))
    )
    (net (code "175") (name "unconnected-(M_FL-NC-PadP24)") (class "Default")
      (node (ref "M_FL") (pin "P24") (pinfunction "NC_P24") (pintype "no_connect"))
    )
    (net (code "176") (name "unconnected-(M_FL-NC-PadP29)") (class "Default")
      (node (ref "M_FL") (pin "P29") (pinfunction "NC_P29") (pintype "no_connect"))
    )
    (net (code "177") (name "unconnected-(M_FR-NC-PadP2)") (class "Default")
      (node (ref "M_FR") (pin "P2") (pinfunction "NC_P2") (pintype "no_connect"))
    )
    (net (code "178") (name "unconnected-(M_FR-NC-PadP14)") (class "Default")
      (node (ref "M_FR") (pin "P14") (pinfunction "NC_P14") (pintype "no_connect"))
    )
    (net (code "179") (name "unconnected-(M_FR-NC-PadP17)") (class "Default")
      (node (ref "M_FR") (pin "P17") (pinfunction "NC_P17") (pintype "no_connect"))
    )
    (net (code "180") (name "unconnected-(M_FR-NC-PadP22)") (class "Default")
      (node (ref "M_FR") (pin "P22") (pinfunction "NC_P22") (pintype "no_connect"))
    )
    (net (code "181") (name "unconnected-(M_FR-NC-PadP24)") (class "Default")
      (node (ref "M_FR") (pin "P24") (pinfunction "NC_P24") (pintype "no_connect"))
    )
    (net (code "182") (name "unconnected-(M_FR-NC-PadP29)") (class "Default")
      (node (ref "M_FR") (pin "P29") (pinfunction "NC_P29") (pintype "no_connect"))
    )
    (net (code "183") (name "unconnected-(S3-S-Pad3)") (class "Default")
      (node (ref "S3") (pin "3") (pinfunction "S_3") (pintype "passive"))
    )
    (net (code "184") (name "unconnected-(U$2-PA11{slash}USART1_CTS{slash}CAN_RX{slash}TIM1_CH4{slash}USBDM-Pad32)") (class "Default")
      (node (ref "U$2") (pin "32") (pinfunction "PA11/USART1_CTS/CAN_RX/TIM1_CH4/USBDM_32") (pintype "bidirectional"))
    )
    (net (code "185") (name "unconnected-(U$2-PA12{slash}USART1_RTS{slash}CAN_TX{slash}TIM1_ETR{slash}USBDP-Pad33)") (class "Default")
      (node (ref "U$2") (pin "33") (pinfunction "PA12/USART1_RTS/CAN_TX/TIM1_ETR/USBDP_33") (pintype "bidirectional"))
    )
    (net (code "186") (name "unconnected-(U$2-PB0{slash}ADC12_IN8{slash}TIM3_CH3-Pad18)") (class "Default")
      (node (ref "U$2") (pin "18") (pinfunction "PB0/ADC12_IN8/TIM3_CH3_18") (pintype "bidirectional"))
    )
    (net (code "187") (name "unconnected-(U$2-PB2{slash}BOOT1-Pad20)") (class "Default")
      (node (ref "U$2") (pin "20") (pinfunction "PB2/BOOT1_20") (pintype "bidirectional"))
    )
    (net (code "188") (name "unconnected-(U$2-PB9{slash}TIM4_CH4-Pad46)") (class "Default")
      (node (ref "U$2") (pin "46") (pinfunction "PB9/TIM4_CH4_46") (pintype "input"))
    )
    (net (code "189") (name "unconnected-(U$2-PC13-TAMPER-RTC-Pad2)") (class "Default")
      (node (ref "U$2") (pin "2") (pinfunction "PC13-TAMPER-RTC_2") (pintype "input"))
    )
    (net (code "190") (name "unconnected-(U$2-PC14-OSC32_IN-Pad3)") (class "Default")
      (node (ref "U$2") (pin "3") (pinfunction "PC14-OSC32_IN_3") (pintype "input"))
    )
    (net (code "191") (name "unconnected-(U$2-PC15-OSC32_OUT-Pad4)") (class "Default")
      (node (ref "U$2") (pin "4") (pinfunction "PC15-OSC32_OUT_4") (pintype "input"))
    )
    (net (code "192") (name "unconnected-(U1-ENA-Pad5)") (class "Default")
      (node (ref "U1") (pin "5") (pinfunction "ENA_5") (pintype "input"))
    )
    (net (code "193") (name "unconnected-(U1-NC-Pad2)") (class "Default")
      (node (ref "U1") (pin "2") (pinfunction "NC_2") (pintype "no_connect"))
    )
    (net (code "194") (name "unconnected-(U1-NC-Pad3)") (class "Default")
      (node (ref "U1") (pin "3") (pinfunction "NC_3") (pintype "no_connect"))
    )
  )
)
